# axiom_beta_plugin_module_TE0714_SDI_v0_1.net
KiCad netlist of a schematic drawn in EAGLE
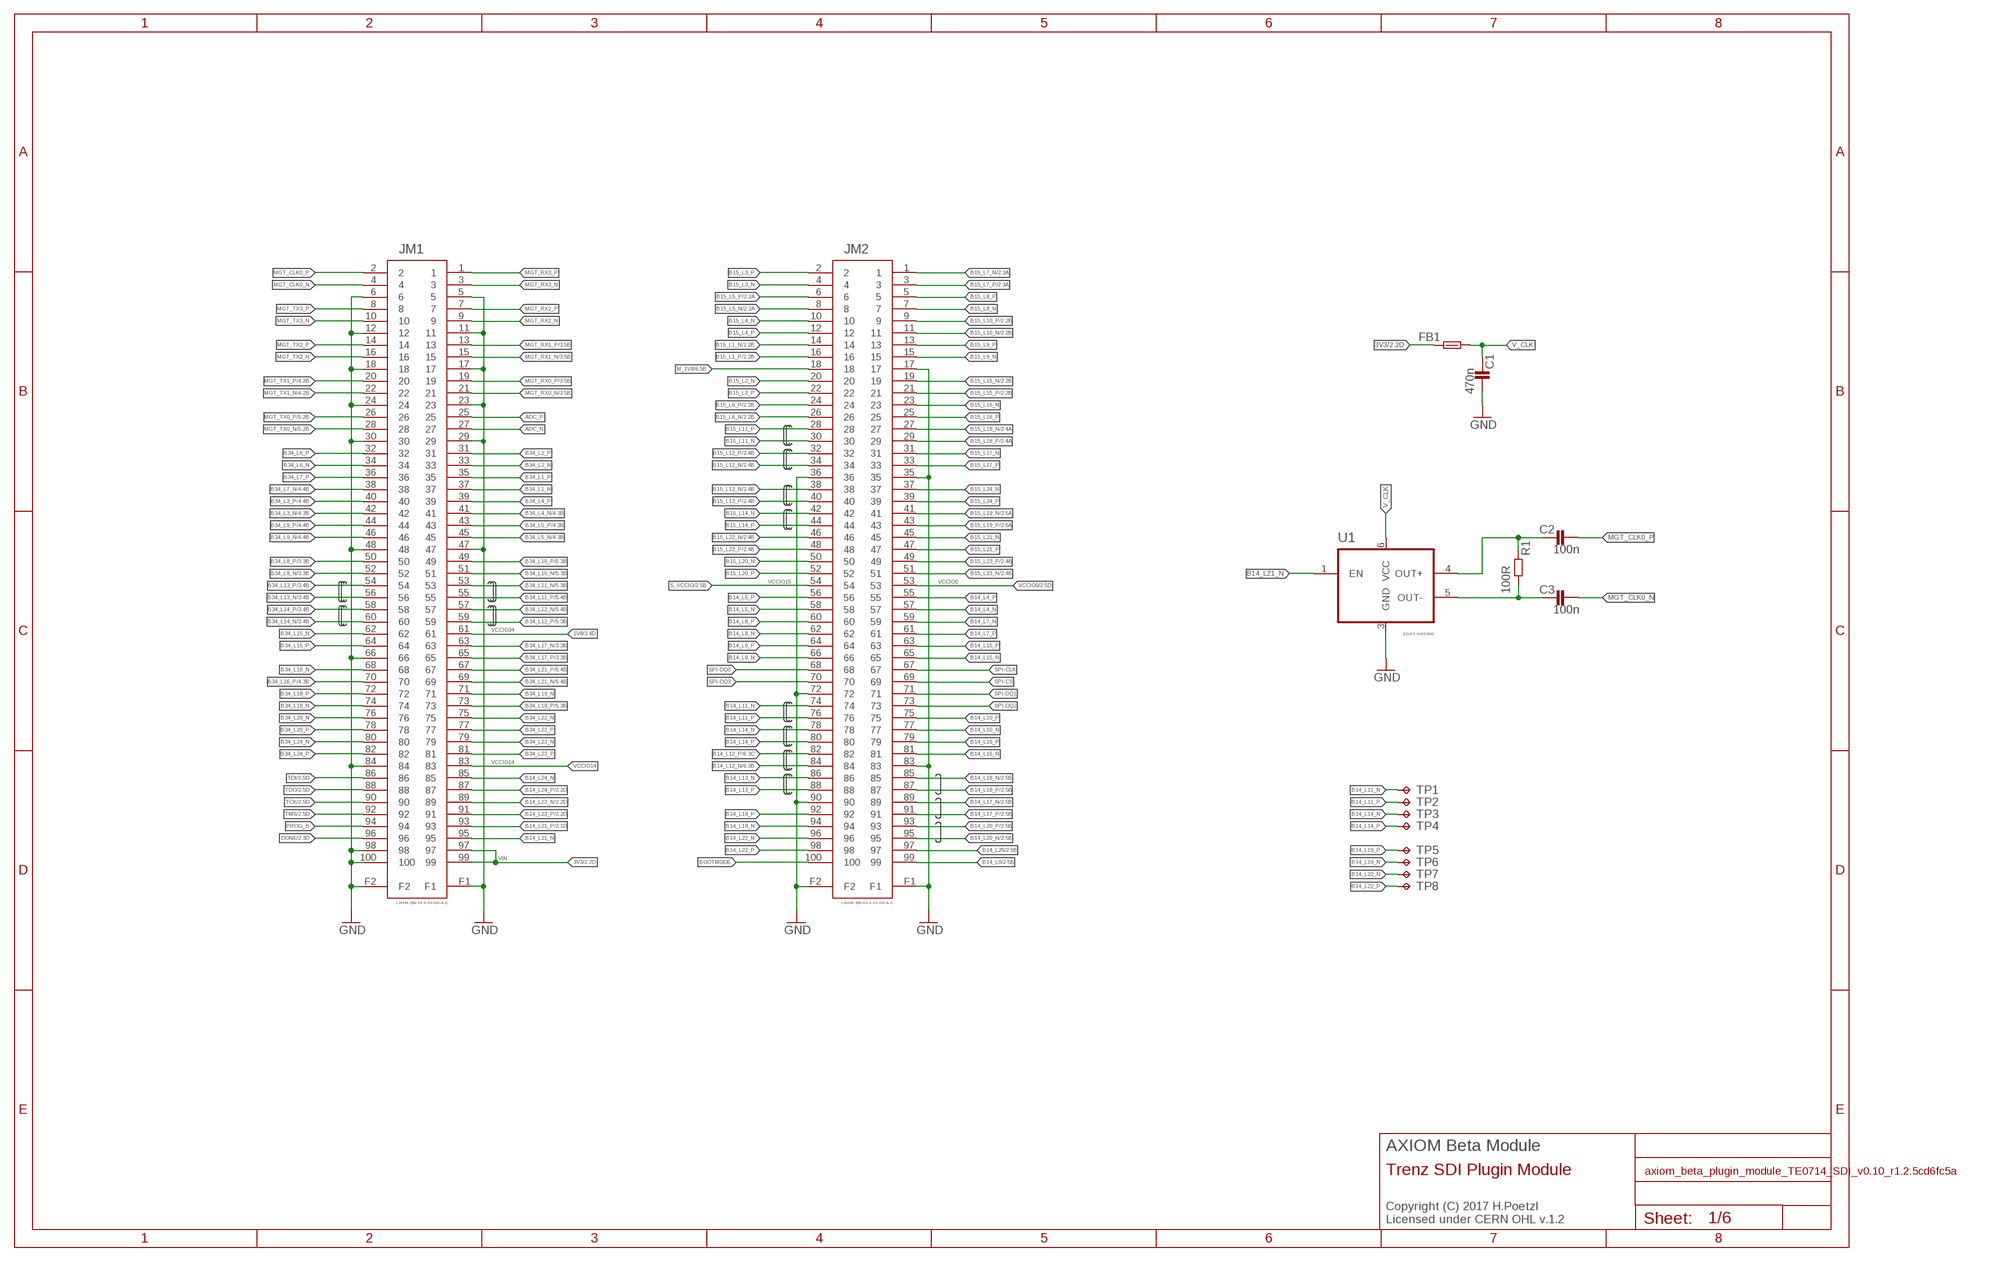
[diagram p0: schematic, sheet 1]
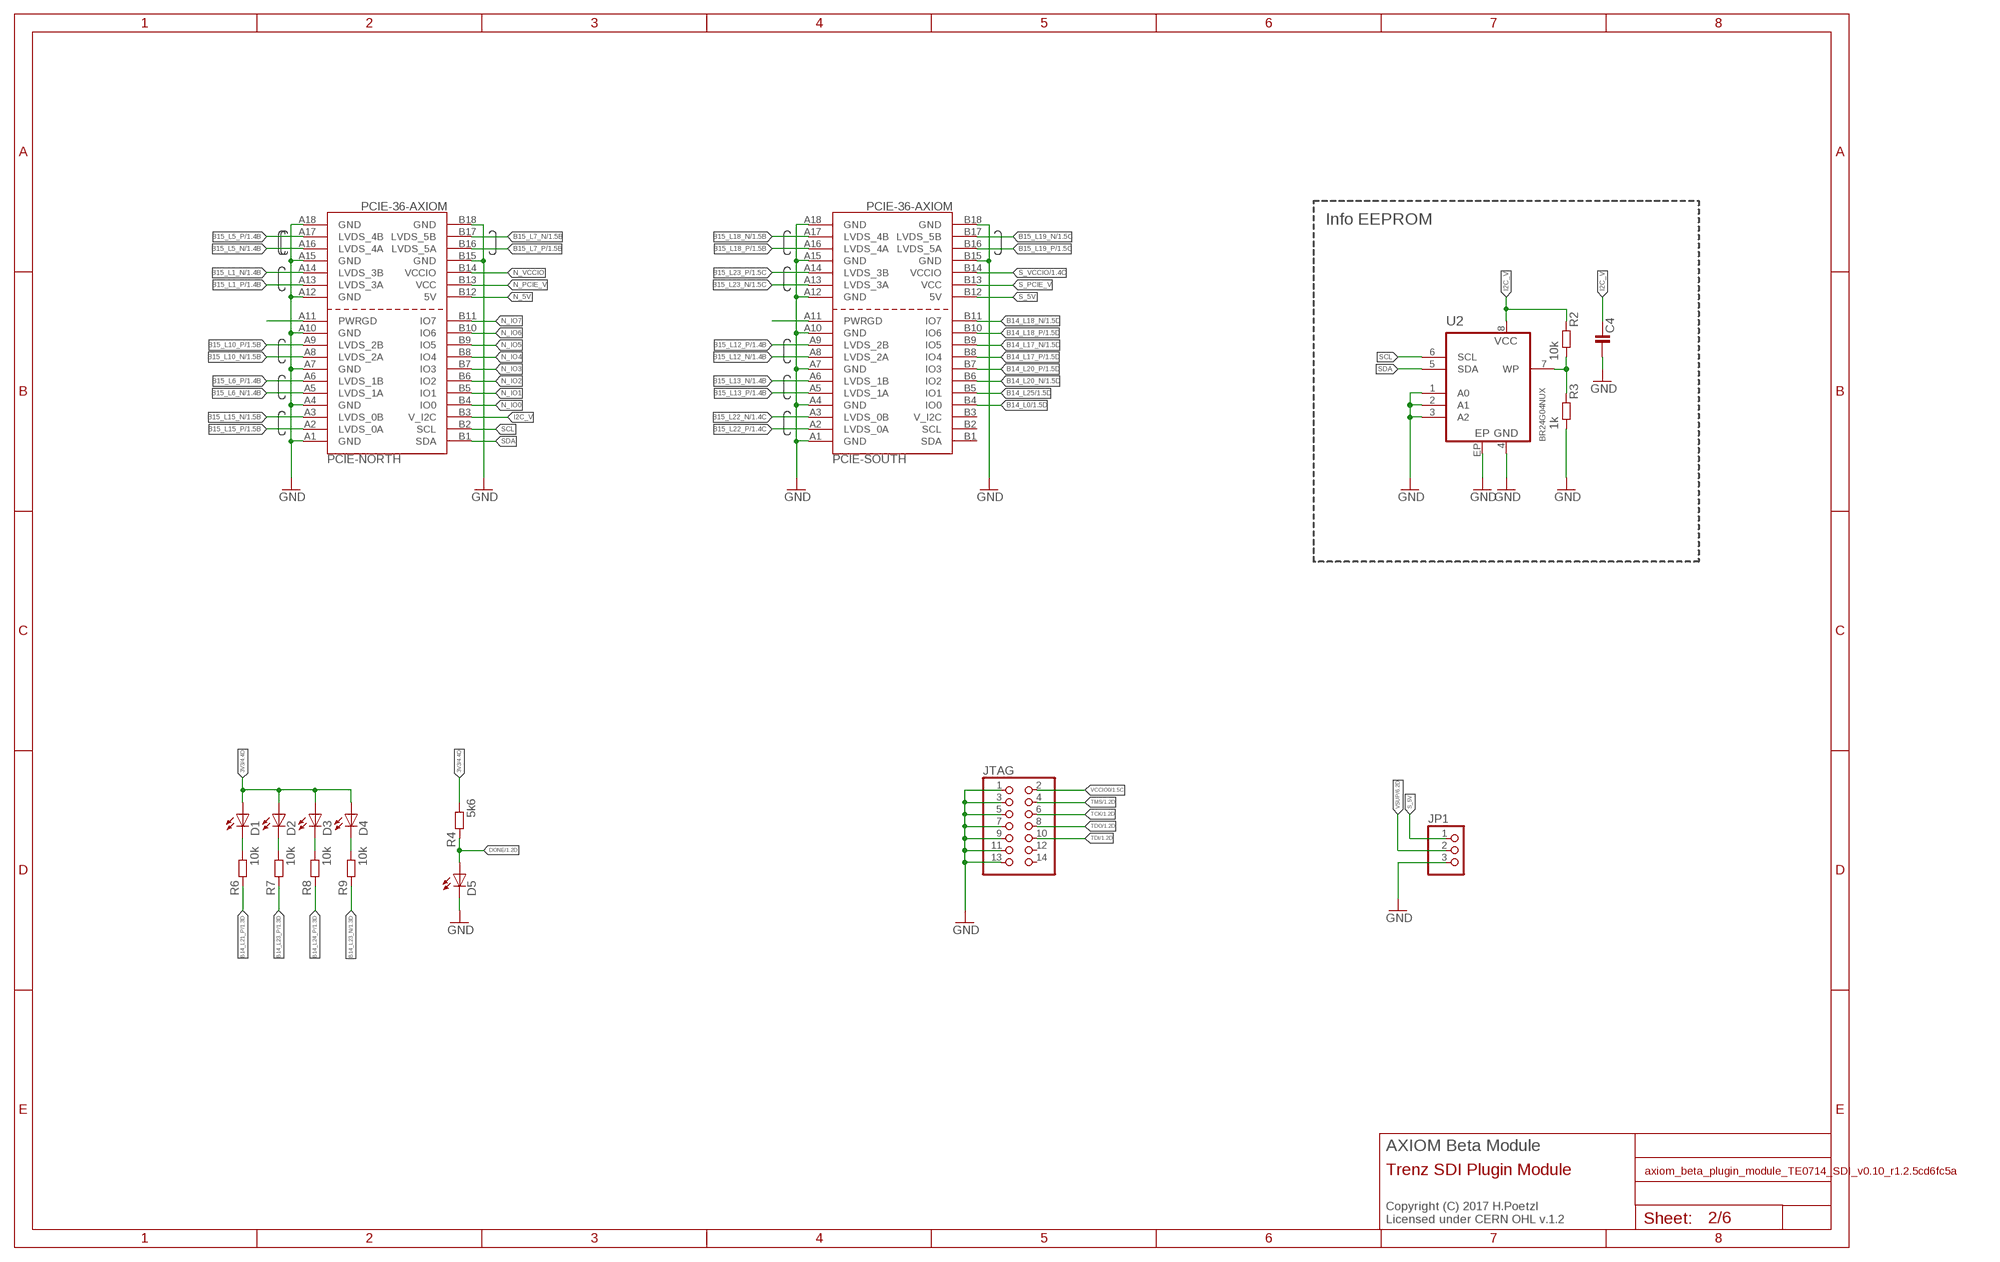
[diagram p1: schematic, sheet 2]
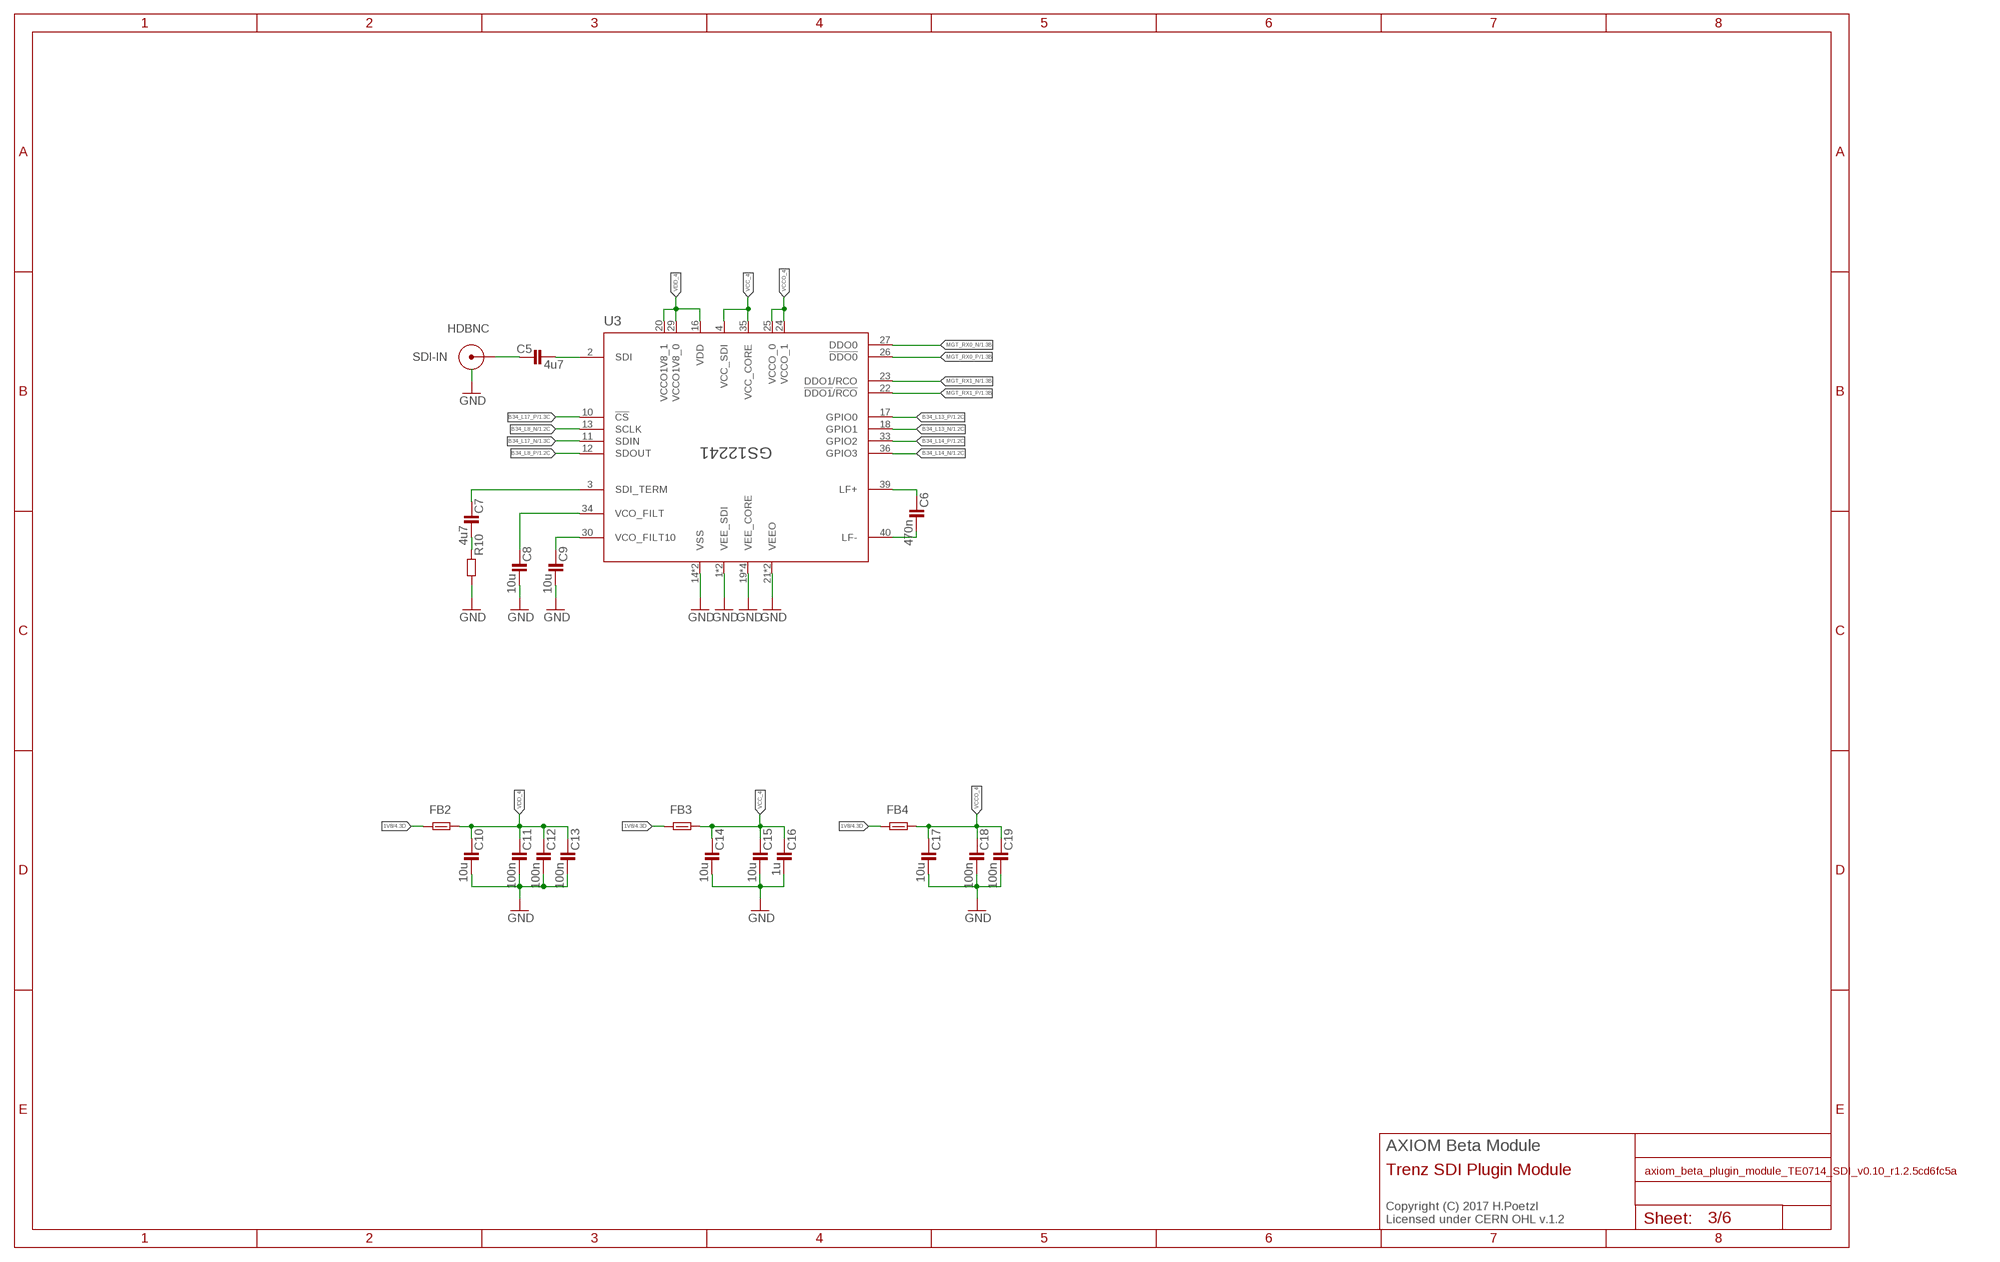
[diagram p2: schematic, sheet 3]
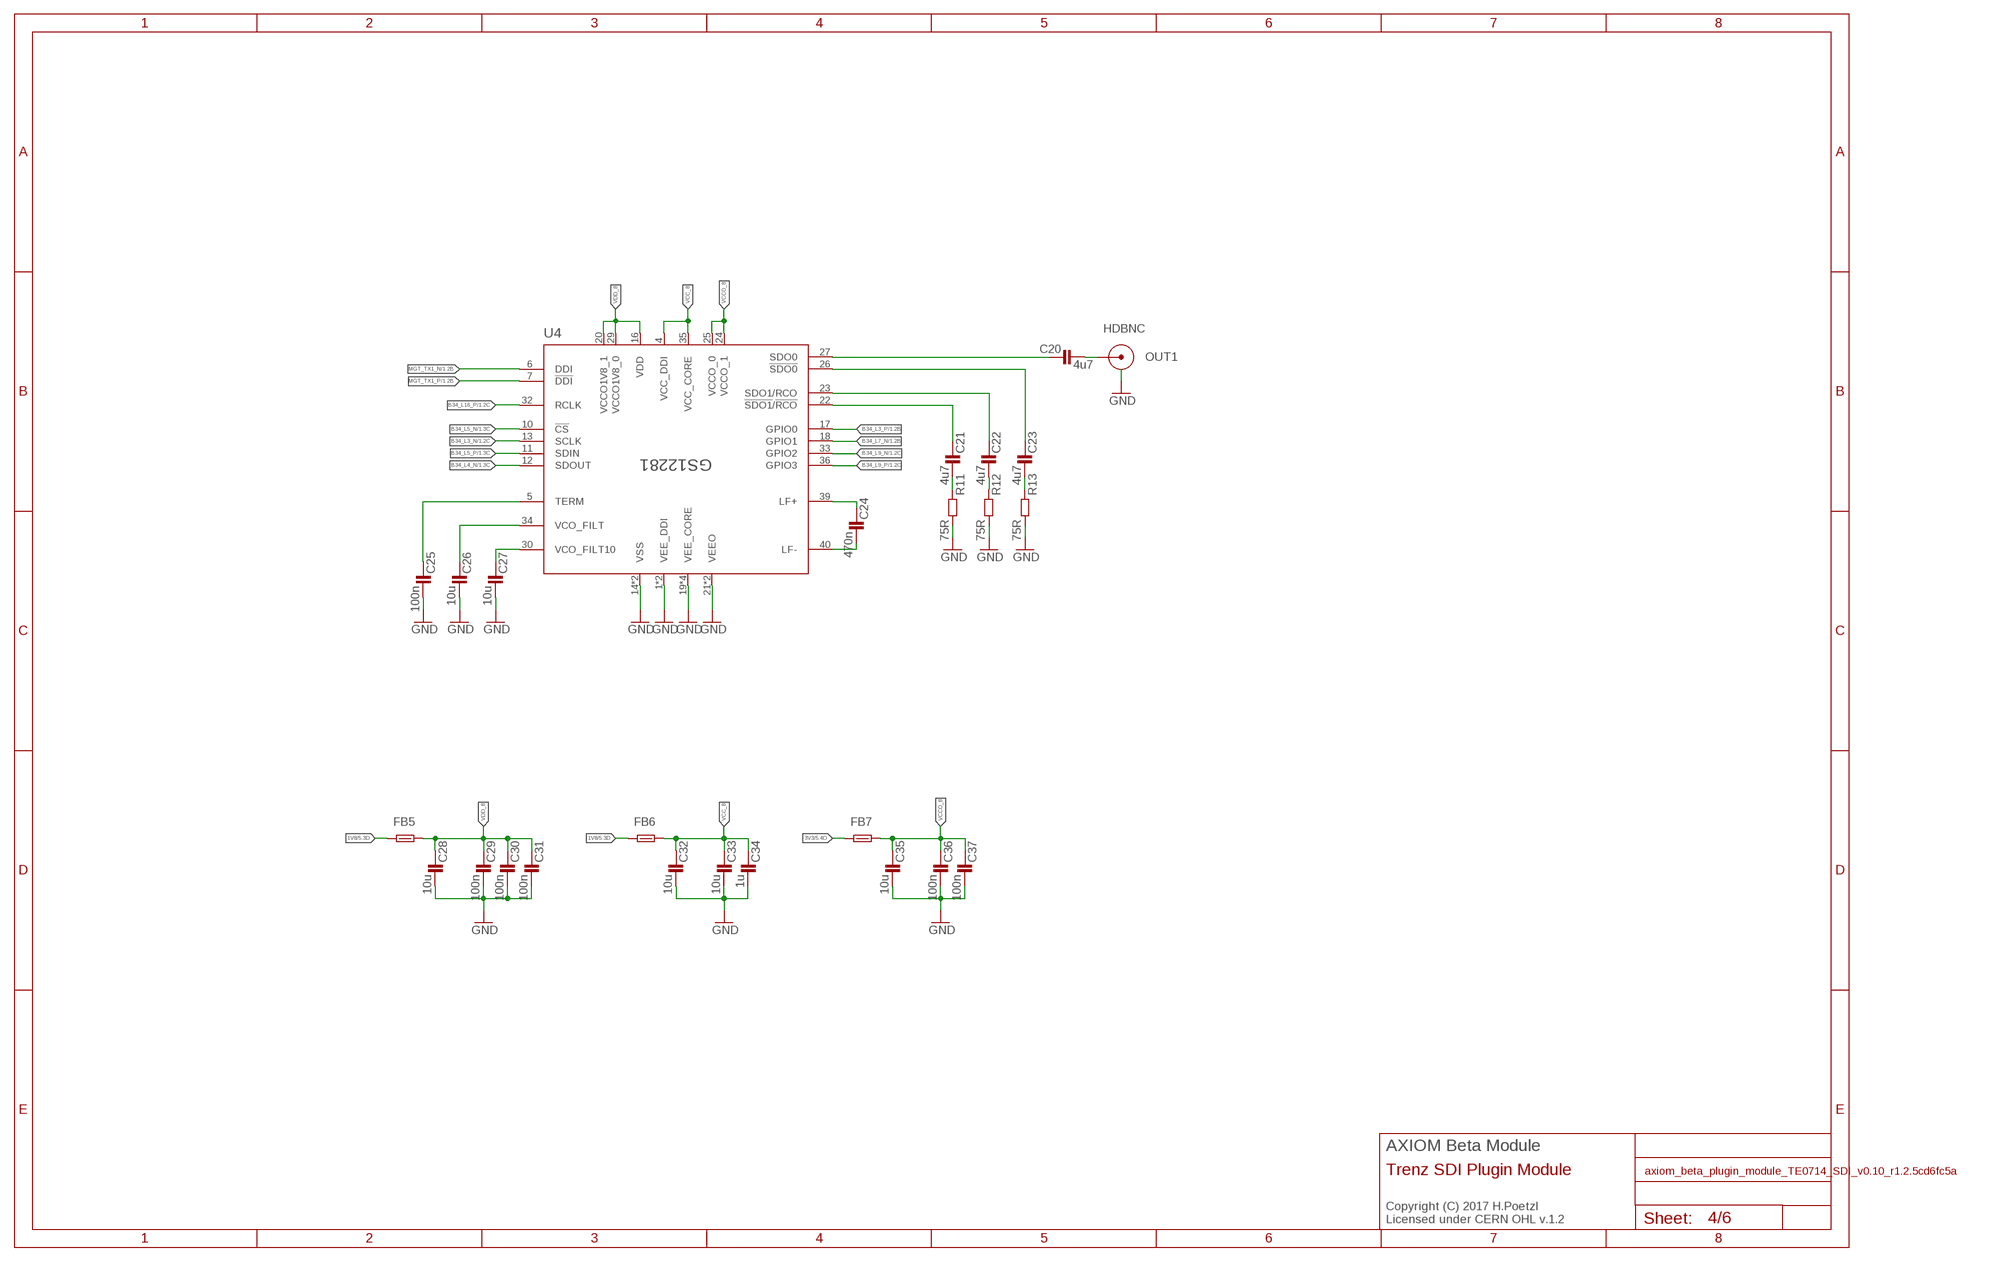
[diagram p3: schematic, sheet 4]
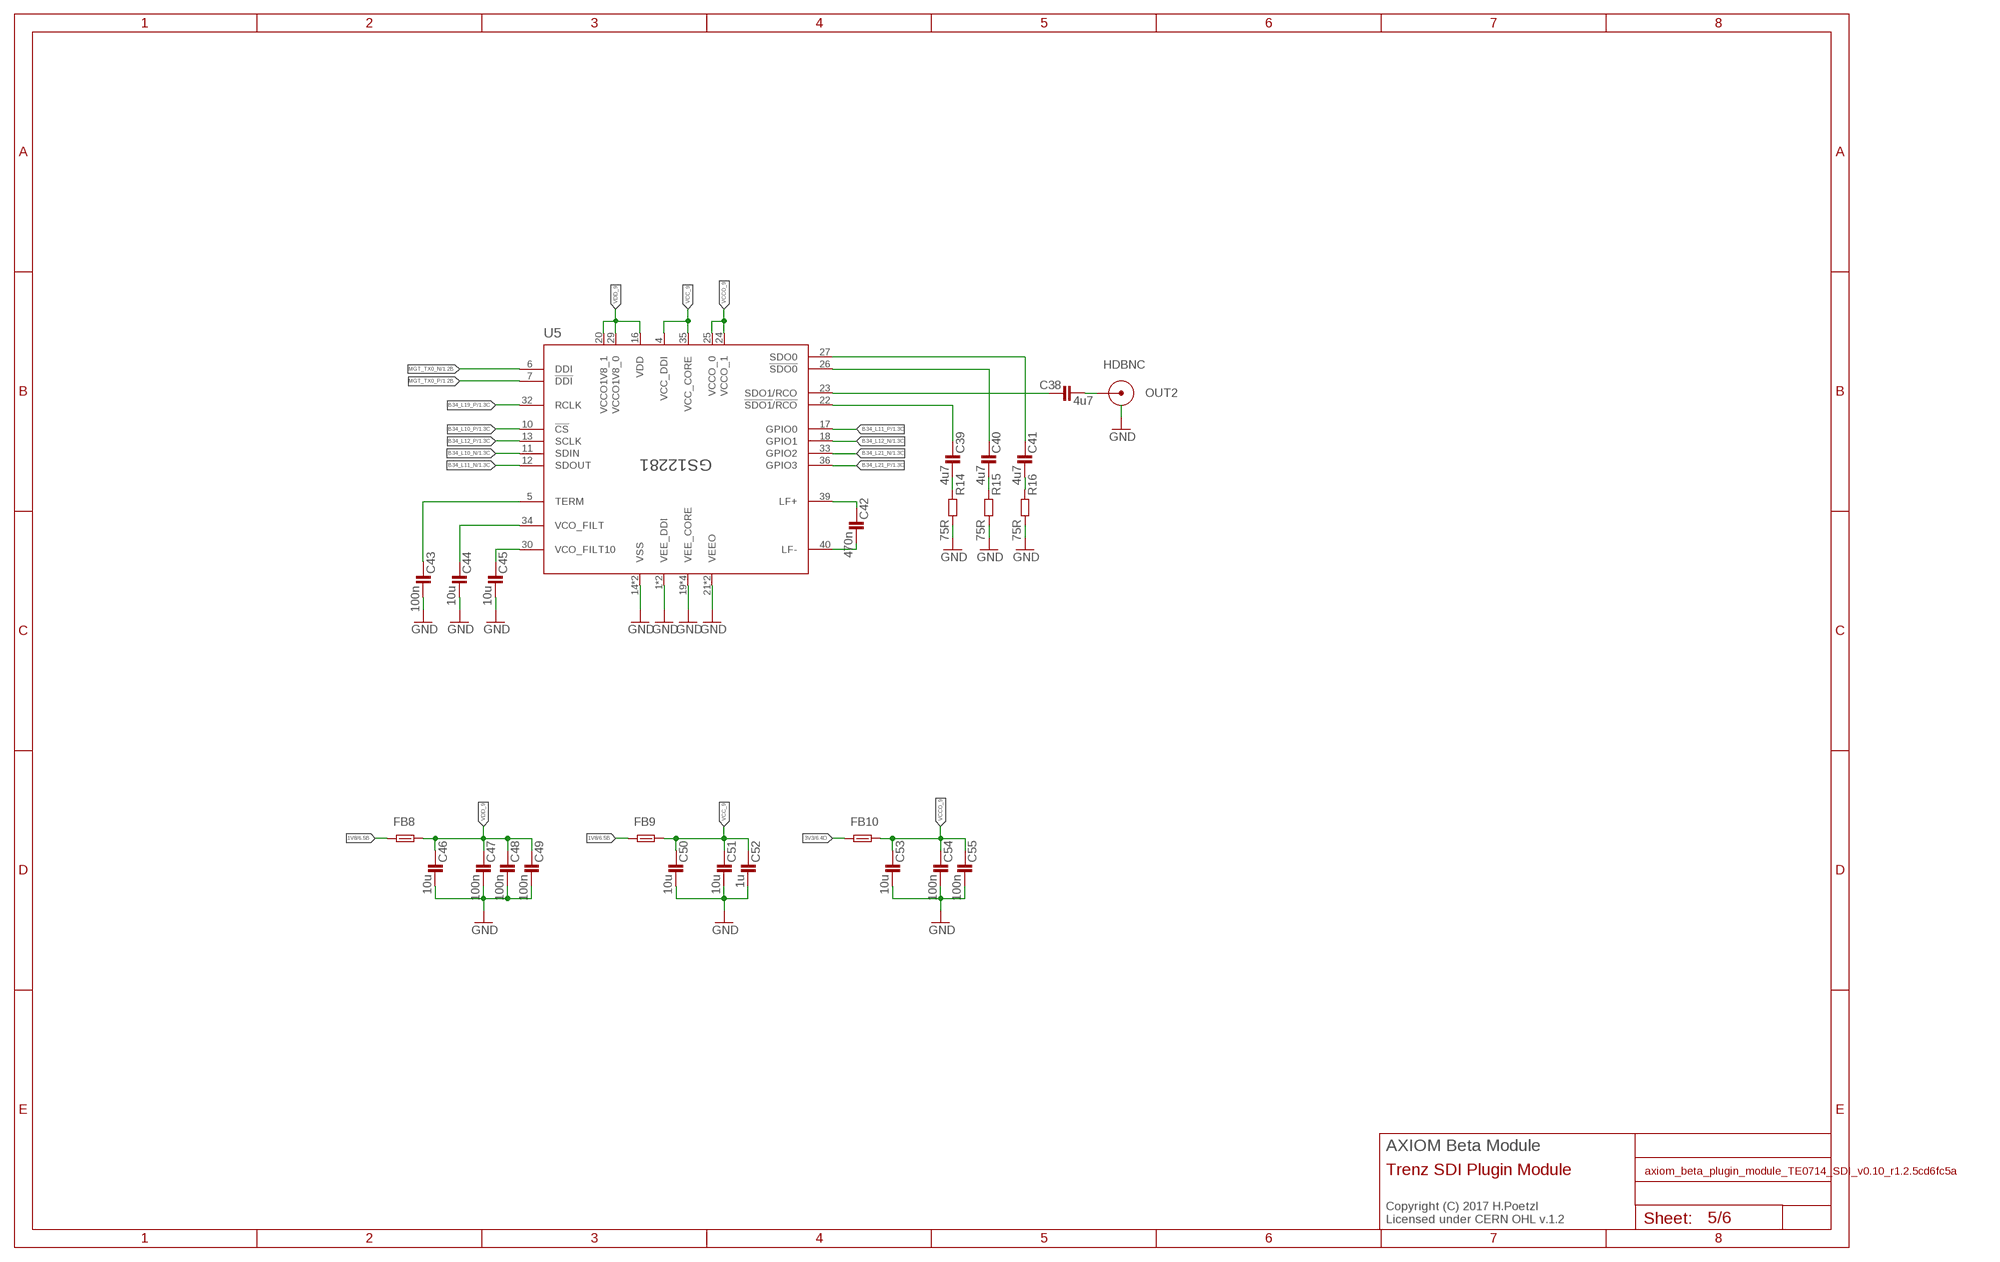
[diagram p4: schematic, sheet 5]
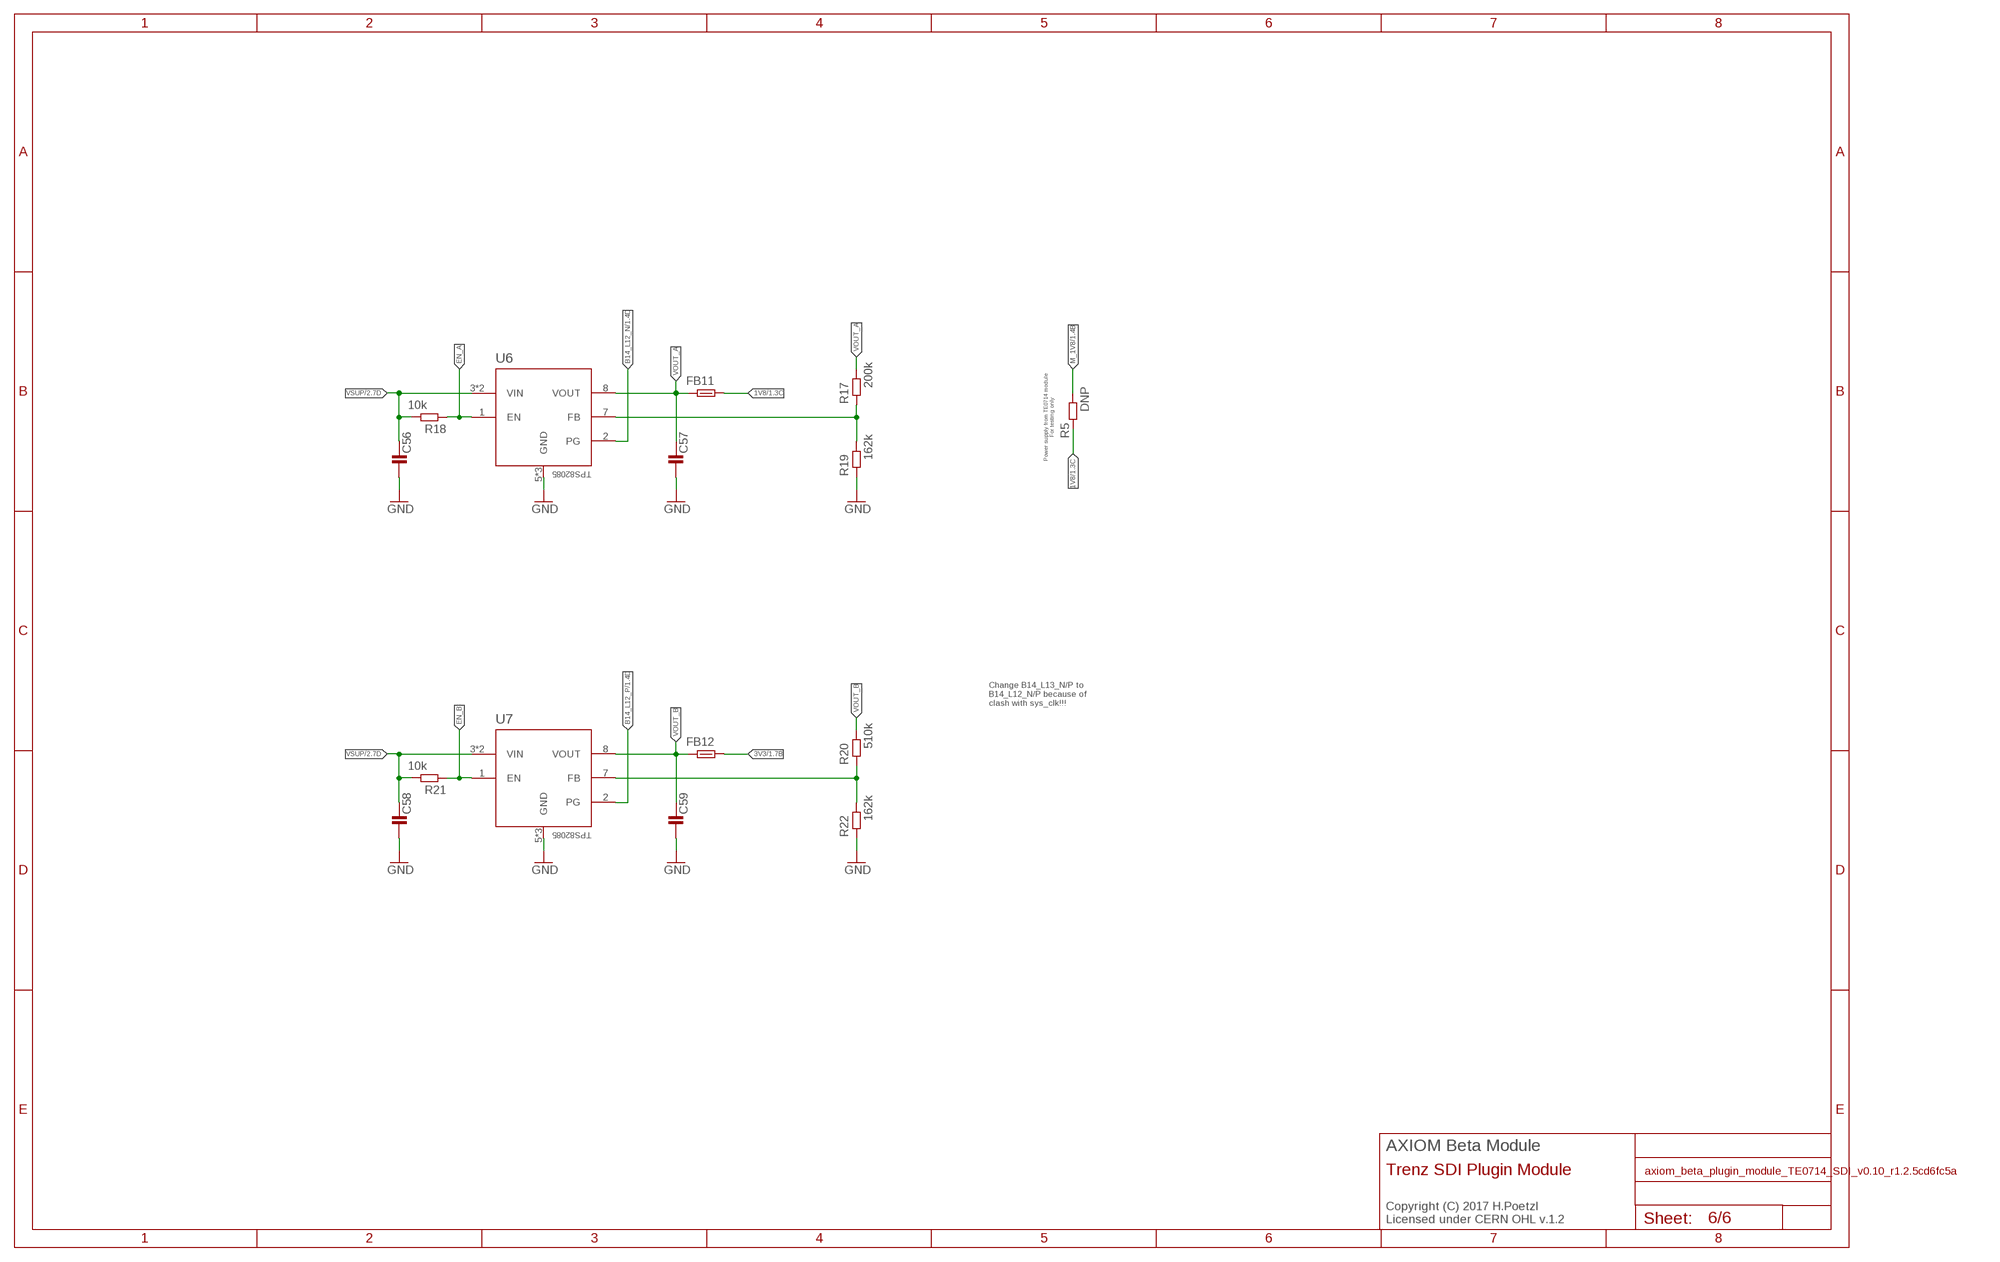
[diagram p5: schematic, sheet 6]

(export (version "E")
  (design (tool "Eeschema 10.0.6"))
  (components
    (comp (ref "C4")
      (value "C0402-B")
      (footprint "eagle-import:0402-B")
      (libsource (lib "eagle-import") (part "C0402-B"))
    )
    (comp (ref "D1")
      (value "LED")
      (footprint "eagle-import:CHIPLED_0603")
      (libsource (lib "eagle-import") (part "LED"))
    )
    (comp (ref "D2")
      (value "LED")
      (footprint "eagle-import:CHIPLED_0603")
      (libsource (lib "eagle-import") (part "LED"))
    )
    (comp (ref "D3")
      (value "LED")
      (footprint "eagle-import:CHIPLED_0603")
      (libsource (lib "eagle-import") (part "LED"))
    )
    (comp (ref "D4")
      (value "LED")
      (footprint "eagle-import:CHIPLED_0603")
      (libsource (lib "eagle-import") (part "LED"))
    )
    (comp (ref "D5")
      (value "LED")
      (footprint "eagle-import:CHIPLED_0603")
      (libsource (lib "eagle-import") (part "LED"))
    )
    (comp (ref "JP1")
      (value "PINHD-1X03_2.54-90°-S")
      (footprint "eagle-import:1X03_90-S")
      (libsource (lib "eagle-import") (part "PINHD-1X03_2.54-90°-S"))
    )
    (comp (ref "JTAG")
      (value "PINHD-2X07_2.00")
      (footprint "eagle-import:2X07M")
      (libsource (lib "eagle-import") (part "PINHD-2X07_2.00"))
    )
    (comp (ref "PCIE-NORTH")
      (value "PCIE-36-AXIOM")
      (footprint "eagle-import:PCIE-36-AXIOM")
      (libsource (lib "eagle-import") (part "PCIE-36-AXIOM"))
    )
    (comp (ref "PCIE-SOUTH")
      (value "PCIE-36-AXIOM")
      (footprint "eagle-import:PCIE-36-AXIOM")
      (libsource (lib "eagle-import") (part "PCIE-36-AXIOM"))
    )
    (comp (ref "R2")
      (value "10k")
      (footprint "eagle-import:0402-B")
      (libsource (lib "eagle-import") (part "R0402-B"))
    )
    (comp (ref "R3")
      (value "1k")
      (footprint "eagle-import:0402-B")
      (libsource (lib "eagle-import") (part "R0402-B"))
    )
    (comp (ref "R4")
      (value "5k6")
      (footprint "eagle-import:0402-C")
      (libsource (lib "eagle-import") (part "R0402-C"))
    )
    (comp (ref "R6")
      (value "10k")
      (footprint "eagle-import:0402-C")
      (libsource (lib "eagle-import") (part "R0402-C"))
    )
    (comp (ref "R7")
      (value "10k")
      (footprint "eagle-import:0402-C")
      (libsource (lib "eagle-import") (part "R0402-C"))
    )
    (comp (ref "R8")
      (value "10k")
      (footprint "eagle-import:0402-C")
      (libsource (lib "eagle-import") (part "R0402-C"))
    )
    (comp (ref "R9")
      (value "10k")
      (footprint "eagle-import:0402-C")
      (libsource (lib "eagle-import") (part "R0402-C"))
    )
    (comp (ref "U2")
      (value "BR24G04NUX")
      (footprint "eagle-import:DFN200X300X100-9N")
      (libsource (lib "eagle-import") (part "BR24G04NUX"))
    )
    (comp (ref "C38")
      (value "4u7")
      (footprint "eagle-import:0402-C")
      (libsource (lib "eagle-import") (part "C0402-C"))
    )
    (comp (ref "C39")
      (value "4u7")
      (footprint "eagle-import:0402-C")
      (libsource (lib "eagle-import") (part "C0402-C"))
    )
    (comp (ref "C40")
      (value "4u7")
      (footprint "eagle-import:0402-C")
      (libsource (lib "eagle-import") (part "C0402-C"))
    )
    (comp (ref "C41")
      (value "4u7")
      (footprint "eagle-import:0402-C")
      (libsource (lib "eagle-import") (part "C0402-C"))
    )
    (comp (ref "C42")
      (value "470n")
      (footprint "eagle-import:0201-C")
      (libsource (lib "eagle-import") (part "C0201-C"))
    )
    (comp (ref "C43")
      (value "100n")
      (footprint "eagle-import:0201-C")
      (libsource (lib "eagle-import") (part "C0201-C"))
    )
    (comp (ref "C44")
      (value "10u")
      (footprint "eagle-import:0402-C")
      (libsource (lib "eagle-import") (part "C0402-C"))
    )
    (comp (ref "C45")
      (value "10u")
      (footprint "eagle-import:0402-C")
      (libsource (lib "eagle-import") (part "C0402-C"))
    )
    (comp (ref "C46")
      (value "10u")
      (footprint "eagle-import:0402-C")
      (libsource (lib "eagle-import") (part "C0402-C"))
    )
    (comp (ref "C47")
      (value "100n")
      (footprint "eagle-import:0201-C")
      (libsource (lib "eagle-import") (part "C0201-C"))
    )
    (comp (ref "C48")
      (value "100n")
      (footprint "eagle-import:0201-C")
      (libsource (lib "eagle-import") (part "C0201-C"))
    )
    (comp (ref "C49")
      (value "100n")
      (footprint "eagle-import:0201-C")
      (libsource (lib "eagle-import") (part "C0201-C"))
    )
    (comp (ref "C50")
      (value "10u")
      (footprint "eagle-import:0402-C")
      (libsource (lib "eagle-import") (part "C0402-C"))
    )
    (comp (ref "C51")
      (value "10u")
      (footprint "eagle-import:0402-C")
      (libsource (lib "eagle-import") (part "C0402-C"))
    )
    (comp (ref "C52")
      (value "1u")
      (footprint "eagle-import:0201-C")
      (libsource (lib "eagle-import") (part "C0201-C"))
    )
    (comp (ref "C53")
      (value "10u")
      (footprint "eagle-import:0402-C")
      (libsource (lib "eagle-import") (part "C0402-C"))
    )
    (comp (ref "C54")
      (value "100n")
      (footprint "eagle-import:0201-C")
      (libsource (lib "eagle-import") (part "C0201-C"))
    )
    (comp (ref "C55")
      (value "100n")
      (footprint "eagle-import:0201-C")
      (libsource (lib "eagle-import") (part "C0201-C"))
    )
    (comp (ref "FB8")
      (value "FB0402-C")
      (footprint "eagle-import:0402-C")
      (libsource (lib "eagle-import") (part "FB0402-C"))
    )
    (comp (ref "FB9")
      (value "FB0402-C")
      (footprint "eagle-import:0402-C")
      (libsource (lib "eagle-import") (part "FB0402-C"))
    )
    (comp (ref "FB10")
      (value "FB0402-C")
      (footprint "eagle-import:0402-C")
      (libsource (lib "eagle-import") (part "FB0402-C"))
    )
    (comp (ref "OUT2")
      (value "HDBNC")
      (footprint "eagle-import:HDBNC_EDGE_2SIDE")
      (libsource (lib "eagle-import") (part "HDBNC"))
    )
    (comp (ref "R14")
      (value "75R")
      (footprint "eagle-import:0201-C")
      (libsource (lib "eagle-import") (part "R0201-C"))
    )
    (comp (ref "R15")
      (value "75R")
      (footprint "eagle-import:0201-C")
      (libsource (lib "eagle-import") (part "R0201-C"))
    )
    (comp (ref "R16")
      (value "75R")
      (footprint "eagle-import:0201-C")
      (libsource (lib "eagle-import") (part "R0201-C"))
    )
    (comp (ref "U5")
      (value "GS12281")
      (footprint "eagle-import:UQFN40P600X400X100-41N")
      (libsource (lib "eagle-import") (part "GS12281"))
    )
    (comp (ref "C1")
      (value "470n")
      (footprint "eagle-import:0402-C")
      (libsource (lib "eagle-import") (part "C0402-C"))
    )
    (comp (ref "C2")
      (value "100n")
      (footprint "eagle-import:0201-C")
      (libsource (lib "eagle-import") (part "C0201-C"))
    )
    (comp (ref "C3")
      (value "100n")
      (footprint "eagle-import:0201-C")
      (libsource (lib "eagle-import") (part "C0201-C"))
    )
    (comp (ref "FB1")
      (value "FB0402-C")
      (footprint "eagle-import:0402-C")
      (libsource (lib "eagle-import") (part "FB0402-C"))
    )
    (comp (ref "JM1")
      (value "LSHM-150-XX.X-XX-DV-A-S")
      (footprint "eagle-import:LSHM-150-XX.X-XX-DV-A-S")
      (libsource (lib "eagle-import") (part "LSHM-150-XX.X-XX-DV-A-S"))
    )
    (comp (ref "JM2")
      (value "LSHM-150-XX.X-XX-DV-A-S")
      (footprint "eagle-import:LSHM-150-XX.X-XX-DV-A-S")
      (libsource (lib "eagle-import") (part "LSHM-150-XX.X-XX-DV-A-S"))
    )
    (comp (ref "R1")
      (value "100R")
      (footprint "eagle-import:0201-C")
      (libsource (lib "eagle-import") (part "R0201-C"))
    )
    (comp (ref "TP1")
      (value "TPTP08R")
      (footprint "eagle-import:TP08R")
      (libsource (lib "eagle-import") (part "TPTP08R"))
    )
    (comp (ref "TP2")
      (value "TPTP08R")
      (footprint "eagle-import:TP08R")
      (libsource (lib "eagle-import") (part "TPTP08R"))
    )
    (comp (ref "TP3")
      (value "TPTP08R")
      (footprint "eagle-import:TP08R")
      (libsource (lib "eagle-import") (part "TPTP08R"))
    )
    (comp (ref "TP4")
      (value "TPTP08R")
      (footprint "eagle-import:TP08R")
      (libsource (lib "eagle-import") (part "TPTP08R"))
    )
    (comp (ref "TP5")
      (value "TPTP10R")
      (footprint "eagle-import:TP10R")
      (libsource (lib "eagle-import") (part "TPTP10R"))
    )
    (comp (ref "TP6")
      (value "TPTP10R")
      (footprint "eagle-import:TP10R")
      (libsource (lib "eagle-import") (part "TPTP10R"))
    )
    (comp (ref "TP7")
      (value "TPTP10R")
      (footprint "eagle-import:TP10R")
      (libsource (lib "eagle-import") (part "TPTP10R"))
    )
    (comp (ref "TP8")
      (value "TPTP10R")
      (footprint "eagle-import:TP10R")
      (libsource (lib "eagle-import") (part "TPTP10R"))
    )
    (comp (ref "U1")
      (value "DSC11XX-3.2X2.5")
      (footprint "eagle-import:3.2X2.5")
      (libsource (lib "eagle-import") (part "DSC11XX-3.2X2.5"))
    )
    (comp (ref "C56")
      (value "C0603-C")
      (footprint "eagle-import:0603-C")
      (libsource (lib "eagle-import") (part "C0603-C"))
    )
    (comp (ref "C57")
      (value "C0603-C")
      (footprint "eagle-import:0603-C")
      (libsource (lib "eagle-import") (part "C0603-C"))
    )
    (comp (ref "C58")
      (value "C0603-C")
      (footprint "eagle-import:0603-C")
      (libsource (lib "eagle-import") (part "C0603-C"))
    )
    (comp (ref "C59")
      (value "C0603-C")
      (footprint "eagle-import:0603-C")
      (libsource (lib "eagle-import") (part "C0603-C"))
    )
    (comp (ref "FB11")
      (value "FB0603-C")
      (footprint "eagle-import:0603-C")
      (libsource (lib "eagle-import") (part "FB0603-C"))
    )
    (comp (ref "FB12")
      (value "FB0603-C")
      (footprint "eagle-import:0603-C")
      (libsource (lib "eagle-import") (part "FB0603-C"))
    )
    (comp (ref "R5")
      (value "DNP")
      (footprint "eagle-import:0402-C")
      (libsource (lib "eagle-import") (part "R0402-C"))
    )
    (comp (ref "R17")
      (value "200k")
      (footprint "eagle-import:0201-C")
      (libsource (lib "eagle-import") (part "R0201-C"))
    )
    (comp (ref "R18")
      (value "10k")
      (footprint "eagle-import:0201-C")
      (libsource (lib "eagle-import") (part "R0201-C"))
    )
    (comp (ref "R19")
      (value "162k")
      (footprint "eagle-import:0201-C")
      (libsource (lib "eagle-import") (part "R0201-C"))
    )
    (comp (ref "R20")
      (value "510k")
      (footprint "eagle-import:0201-C")
      (libsource (lib "eagle-import") (part "R0201-C"))
    )
    (comp (ref "R21")
      (value "10k")
      (footprint "eagle-import:0201-C")
      (libsource (lib "eagle-import") (part "R0201-C"))
    )
    (comp (ref "R22")
      (value "162k")
      (footprint "eagle-import:0201-C")
      (libsource (lib "eagle-import") (part "R0201-C"))
    )
    (comp (ref "U6")
      (value "TPS82085")
      (footprint "eagle-import:MICROSIP")
      (libsource (lib "eagle-import") (part "TPS82085"))
    )
    (comp (ref "U7")
      (value "TPS82085")
      (footprint "eagle-import:MICROSIP")
      (libsource (lib "eagle-import") (part "TPS82085"))
    )
    (comp (ref "C20")
      (value "4u7")
      (footprint "eagle-import:0402-C")
      (libsource (lib "eagle-import") (part "C0402-C"))
    )
    (comp (ref "C21")
      (value "4u7")
      (footprint "eagle-import:0402-C")
      (libsource (lib "eagle-import") (part "C0402-C"))
    )
    (comp (ref "C22")
      (value "4u7")
      (footprint "eagle-import:0402-C")
      (libsource (lib "eagle-import") (part "C0402-C"))
    )
    (comp (ref "C23")
      (value "4u7")
      (footprint "eagle-import:0402-C")
      (libsource (lib "eagle-import") (part "C0402-C"))
    )
    (comp (ref "C24")
      (value "470n")
      (footprint "eagle-import:0201-C")
      (libsource (lib "eagle-import") (part "C0201-C"))
    )
    (comp (ref "C25")
      (value "100n")
      (footprint "eagle-import:0201-C")
      (libsource (lib "eagle-import") (part "C0201-C"))
    )
    (comp (ref "C26")
      (value "10u")
      (footprint "eagle-import:0402-C")
      (libsource (lib "eagle-import") (part "C0402-C"))
    )
    (comp (ref "C27")
      (value "10u")
      (footprint "eagle-import:0402-C")
      (libsource (lib "eagle-import") (part "C0402-C"))
    )
    (comp (ref "C28")
      (value "10u")
      (footprint "eagle-import:0402-C")
      (libsource (lib "eagle-import") (part "C0402-C"))
    )
    (comp (ref "C29")
      (value "100n")
      (footprint "eagle-import:0201-C")
      (libsource (lib "eagle-import") (part "C0201-C"))
    )
    (comp (ref "C30")
      (value "100n")
      (footprint "eagle-import:0201-C")
      (libsource (lib "eagle-import") (part "C0201-C"))
    )
    (comp (ref "C31")
      (value "100n")
      (footprint "eagle-import:0201-C")
      (libsource (lib "eagle-import") (part "C0201-C"))
    )
    (comp (ref "C32")
      (value "10u")
      (footprint "eagle-import:0402-C")
      (libsource (lib "eagle-import") (part "C0402-C"))
    )
    (comp (ref "C33")
      (value "10u")
      (footprint "eagle-import:0402-C")
      (libsource (lib "eagle-import") (part "C0402-C"))
    )
    (comp (ref "C34")
      (value "1u")
      (footprint "eagle-import:0201-C")
      (libsource (lib "eagle-import") (part "C0201-C"))
    )
    (comp (ref "C35")
      (value "10u")
      (footprint "eagle-import:0402-C")
      (libsource (lib "eagle-import") (part "C0402-C"))
    )
    (comp (ref "C36")
      (value "100n")
      (footprint "eagle-import:0201-C")
      (libsource (lib "eagle-import") (part "C0201-C"))
    )
    (comp (ref "C37")
      (value "100n")
      (footprint "eagle-import:0201-C")
      (libsource (lib "eagle-import") (part "C0201-C"))
    )
    (comp (ref "FB5")
      (value "FB0402-C")
      (footprint "eagle-import:0402-C")
      (libsource (lib "eagle-import") (part "FB0402-C"))
    )
    (comp (ref "FB6")
      (value "FB0402-C")
      (footprint "eagle-import:0402-C")
      (libsource (lib "eagle-import") (part "FB0402-C"))
    )
    (comp (ref "FB7")
      (value "FB0402-C")
      (footprint "eagle-import:0402-C")
      (libsource (lib "eagle-import") (part "FB0402-C"))
    )
    (comp (ref "OUT1")
      (value "HDBNC")
      (footprint "eagle-import:HDBNC_EDGE_2SIDE")
      (libsource (lib "eagle-import") (part "HDBNC"))
    )
    (comp (ref "R11")
      (value "75R")
      (footprint "eagle-import:0201-C")
      (libsource (lib "eagle-import") (part "R0201-C"))
    )
    (comp (ref "R12")
      (value "75R")
      (footprint "eagle-import:0201-C")
      (libsource (lib "eagle-import") (part "R0201-C"))
    )
    (comp (ref "R13")
      (value "75R")
      (footprint "eagle-import:0201-C")
      (libsource (lib "eagle-import") (part "R0201-C"))
    )
    (comp (ref "U4")
      (value "GS12281")
      (footprint "eagle-import:UQFN40P600X400X100-41N")
      (libsource (lib "eagle-import") (part "GS12281"))
    )
    (comp (ref "C5")
      (value "4u7")
      (footprint "eagle-import:0402-C")
      (libsource (lib "eagle-import") (part "C0402-C"))
    )
    (comp (ref "C6")
      (value "470n")
      (footprint "eagle-import:0201-C")
      (libsource (lib "eagle-import") (part "C0201-C"))
    )
    (comp (ref "C7")
      (value "4u7")
      (footprint "eagle-import:0402-C")
      (libsource (lib "eagle-import") (part "C0402-C"))
    )
    (comp (ref "C8")
      (value "10u")
      (footprint "eagle-import:0402-C")
      (libsource (lib "eagle-import") (part "C0402-C"))
    )
    (comp (ref "C9")
      (value "10u")
      (footprint "eagle-import:0402-C")
      (libsource (lib "eagle-import") (part "C0402-C"))
    )
    (comp (ref "C10")
      (value "10u")
      (footprint "eagle-import:0402-C")
      (libsource (lib "eagle-import") (part "C0402-C"))
    )
    (comp (ref "C11")
      (value "100n")
      (footprint "eagle-import:0201-C")
      (libsource (lib "eagle-import") (part "C0201-C"))
    )
    (comp (ref "C12")
      (value "100n")
      (footprint "eagle-import:0201-C")
      (libsource (lib "eagle-import") (part "C0201-C"))
    )
    (comp (ref "C13")
      (value "100n")
      (footprint "eagle-import:0201-C")
      (libsource (lib "eagle-import") (part "C0201-C"))
    )
    (comp (ref "C14")
      (value "10u")
      (footprint "eagle-import:0402-C")
      (libsource (lib "eagle-import") (part "C0402-C"))
    )
    (comp (ref "C15")
      (value "10u")
      (footprint "eagle-import:0402-C")
      (libsource (lib "eagle-import") (part "C0402-C"))
    )
    (comp (ref "C16")
      (value "1u")
      (footprint "eagle-import:0201-C")
      (libsource (lib "eagle-import") (part "C0201-C"))
    )
    (comp (ref "C17")
      (value "10u")
      (footprint "eagle-import:0402-C")
      (libsource (lib "eagle-import") (part "C0402-C"))
    )
    (comp (ref "C18")
      (value "100n")
      (footprint "eagle-import:0201-C")
      (libsource (lib "eagle-import") (part "C0201-C"))
    )
    (comp (ref "C19")
      (value "100n")
      (footprint "eagle-import:0201-C")
      (libsource (lib "eagle-import") (part "C0201-C"))
    )
    (comp (ref "FB2")
      (value "FB0402-C")
      (footprint "eagle-import:0402-C")
      (libsource (lib "eagle-import") (part "FB0402-C"))
    )
    (comp (ref "FB3")
      (value "FB0402-C")
      (footprint "eagle-import:0402-C")
      (libsource (lib "eagle-import") (part "FB0402-C"))
    )
    (comp (ref "FB4")
      (value "FB0402-C")
      (footprint "eagle-import:0402-C")
      (libsource (lib "eagle-import") (part "FB0402-C"))
    )
    (comp (ref "R10")
      (value "R0201-C")
      (footprint "eagle-import:0201-C")
      (libsource (lib "eagle-import") (part "R0201-C"))
    )
    (comp (ref "SDI-IN")
      (value "HDBNC")
      (footprint "eagle-import:HDBNC_EDGE_2SIDE")
      (libsource (lib "eagle-import") (part "HDBNC"))
    )
    (comp (ref "U3")
      (value "GS12241")
      (footprint "eagle-import:UQFN40P600X400X100-41N")
      (libsource (lib "eagle-import") (part "GS12241"))
    )
  )
  (nets
    (net (code "1") (name "1V8") (class "Default")
      (node (ref "FB11") (pin "2") (pinfunction "2_2") (pintype "passive"))
      (node (ref "FB2") (pin "1") (pinfunction "1_1") (pintype "passive"))
      (node (ref "FB3") (pin "1") (pinfunction "1_1") (pintype "passive"))
      (node (ref "FB4") (pin "1") (pinfunction "1_1") (pintype "passive"))
      (node (ref "FB5") (pin "1") (pinfunction "1_1") (pintype "passive"))
      (node (ref "FB6") (pin "1") (pinfunction "1_1") (pintype "passive"))
      (node (ref "FB8") (pin "1") (pinfunction "1_1") (pintype "passive"))
      (node (ref "FB9") (pin "1") (pinfunction "1_1") (pintype "passive"))
      (node (ref "JM1") (pin "61") (pinfunction "61_61") (pintype "bidirectional"))
      (node (ref "R5") (pin "1") (pinfunction "1_1") (pintype "passive"))
    )
    (net (code "2") (name "3V3") (class "Default")
      (node (ref "D1") (pin "A") (pinfunction "A_A") (pintype "passive"))
      (node (ref "D2") (pin "A") (pinfunction "A_A") (pintype "passive"))
      (node (ref "D3") (pin "A") (pinfunction "A_A") (pintype "passive"))
      (node (ref "D4") (pin "A") (pinfunction "A_A") (pintype "passive"))
      (node (ref "FB1") (pin "1") (pinfunction "1_1") (pintype "passive"))
      (node (ref "FB10") (pin "1") (pinfunction "1_1") (pintype "passive"))
      (node (ref "FB12") (pin "2") (pinfunction "2_2") (pintype "passive"))
      (node (ref "FB7") (pin "1") (pinfunction "1_1") (pintype "passive"))
      (node (ref "JM1") (pin "97") (pinfunction "97_97") (pintype "bidirectional"))
      (node (ref "JM1") (pin "99") (pinfunction "99_99") (pintype "bidirectional"))
      (node (ref "R4") (pin "2") (pinfunction "2_2") (pintype "passive"))
    )
    (net (code "3") (name "ADC_N") (class "Default")
      (node (ref "JM1") (pin "27") (pinfunction "27_27") (pintype "bidirectional"))
    )
    (net (code "4") (name "ADC_P") (class "Default")
      (node (ref "JM1") (pin "25") (pinfunction "25_25") (pintype "bidirectional"))
    )
    (net (code "5") (name "B14_L0") (class "Default")
      (node (ref "JM2") (pin "99") (pinfunction "99_99") (pintype "bidirectional"))
      (node (ref "PCIE-SOUTH") (pin "B4") (pinfunction "IO0_B4") (pintype "passive"))
    )
    (net (code "6") (name "B14_L4_N") (class "Default")
      (node (ref "JM2") (pin "57") (pinfunction "57_57") (pintype "bidirectional"))
    )
    (net (code "7") (name "B14_L4_P") (class "Default")
      (node (ref "JM2") (pin "55") (pinfunction "55_55") (pintype "bidirectional"))
    )
    (net (code "8") (name "B14_L5_N") (class "Default")
      (node (ref "JM2") (pin "58") (pinfunction "58_58") (pintype "bidirectional"))
    )
    (net (code "9") (name "B14_L5_P") (class "Default")
      (node (ref "JM2") (pin "56") (pinfunction "56_56") (pintype "bidirectional"))
    )
    (net (code "10") (name "B14_L7_N") (class "Default")
      (node (ref "JM2") (pin "59") (pinfunction "59_59") (pintype "bidirectional"))
    )
    (net (code "11") (name "B14_L7_P") (class "Default")
      (node (ref "JM2") (pin "61") (pinfunction "61_61") (pintype "bidirectional"))
    )
    (net (code "12") (name "B14_L8_N") (class "Default")
      (node (ref "JM2") (pin "62") (pinfunction "62_62") (pintype "bidirectional"))
    )
    (net (code "13") (name "B14_L8_P") (class "Default")
      (node (ref "JM2") (pin "60") (pinfunction "60_60") (pintype "bidirectional"))
    )
    (net (code "14") (name "B14_L9_N") (class "Default")
      (node (ref "JM2") (pin "66") (pinfunction "66_66") (pintype "bidirectional"))
    )
    (net (code "15") (name "B14_L9_P") (class "Default")
      (node (ref "JM2") (pin "64") (pinfunction "64_64") (pintype "bidirectional"))
    )
    (net (code "16") (name "B14_L10_N") (class "Default")
      (node (ref "JM2") (pin "77") (pinfunction "77_77") (pintype "bidirectional"))
    )
    (net (code "17") (name "B14_L10_P") (class "Default")
      (node (ref "JM2") (pin "75") (pinfunction "75_75") (pintype "bidirectional"))
    )
    (net (code "18") (name "B14_L11_N") (class "Default")
      (node (ref "JM2") (pin "74") (pinfunction "74_74") (pintype "bidirectional"))
      (node (ref "TP1") (pin "TP") (pinfunction "TP_TP") (pintype "input"))
    )
    (net (code "19") (name "B14_L11_P") (class "Default")
      (node (ref "JM2") (pin "76") (pinfunction "76_76") (pintype "bidirectional"))
      (node (ref "TP2") (pin "TP") (pinfunction "TP_TP") (pintype "input"))
    )
    (net (code "20") (name "B14_L12_N") (class "Default")
      (node (ref "JM2") (pin "84") (pinfunction "84_84") (pintype "bidirectional"))
      (node (ref "U6") (pin "2") (pinfunction "PG_2") (pintype "power_in"))
    )
    (net (code "21") (name "B14_L12_P") (class "Default")
      (node (ref "JM2") (pin "82") (pinfunction "82_82") (pintype "bidirectional"))
      (node (ref "U7") (pin "2") (pinfunction "PG_2") (pintype "power_in"))
    )
    (net (code "22") (name "B14_L13_N") (class "Default")
      (node (ref "JM2") (pin "86") (pinfunction "86_86") (pintype "bidirectional"))
    )
    (net (code "23") (name "B14_L13_P") (class "Default")
      (node (ref "JM2") (pin "88") (pinfunction "88_88") (pintype "bidirectional"))
    )
    (net (code "24") (name "B14_L14_N") (class "Default")
      (node (ref "JM2") (pin "78") (pinfunction "78_78") (pintype "bidirectional"))
      (node (ref "TP3") (pin "TP") (pinfunction "TP_TP") (pintype "input"))
    )
    (net (code "25") (name "B14_L14_P") (class "Default")
      (node (ref "JM2") (pin "80") (pinfunction "80_80") (pintype "bidirectional"))
      (node (ref "TP4") (pin "TP") (pinfunction "TP_TP") (pintype "input"))
    )
    (net (code "26") (name "B14_L15_N") (class "Default")
      (node (ref "JM2") (pin "65") (pinfunction "65_65") (pintype "bidirectional"))
    )
    (net (code "27") (name "B14_L15_P") (class "Default")
      (node (ref "JM2") (pin "63") (pinfunction "63_63") (pintype "bidirectional"))
    )
    (net (code "28") (name "B14_L16_N") (class "Default")
      (node (ref "JM2") (pin "81") (pinfunction "81_81") (pintype "bidirectional"))
    )
    (net (code "29") (name "B14_L16_P") (class "Default")
      (node (ref "JM2") (pin "79") (pinfunction "79_79") (pintype "bidirectional"))
    )
    (net (code "30") (name "B14_L17_N") (class "Default")
      (node (ref "JM2") (pin "89") (pinfunction "89_89") (pintype "bidirectional"))
      (node (ref "PCIE-SOUTH") (pin "B9") (pinfunction "IO5_B9") (pintype "passive"))
    )
    (net (code "31") (name "B14_L17_P") (class "Default")
      (node (ref "JM2") (pin "91") (pinfunction "91_91") (pintype "bidirectional"))
      (node (ref "PCIE-SOUTH") (pin "B8") (pinfunction "IO4_B8") (pintype "passive"))
    )
    (net (code "32") (name "B14_L18_N") (class "Default")
      (node (ref "JM2") (pin "85") (pinfunction "85_85") (pintype "bidirectional"))
      (node (ref "PCIE-SOUTH") (pin "B11") (pinfunction "IO7_B11") (pintype "passive"))
    )
    (net (code "33") (name "B14_L18_P") (class "Default")
      (node (ref "JM2") (pin "87") (pinfunction "87_87") (pintype "bidirectional"))
      (node (ref "PCIE-SOUTH") (pin "B10") (pinfunction "IO6_B10") (pintype "passive"))
    )
    (net (code "34") (name "B14_L19_N") (class "Default")
      (node (ref "JM2") (pin "94") (pinfunction "94_94") (pintype "bidirectional"))
      (node (ref "TP6") (pin "TP") (pinfunction "TP_TP") (pintype "input"))
    )
    (net (code "35") (name "B14_L19_P") (class "Default")
      (node (ref "JM2") (pin "92") (pinfunction "92_92") (pintype "bidirectional"))
      (node (ref "TP5") (pin "TP") (pinfunction "TP_TP") (pintype "input"))
    )
    (net (code "36") (name "B14_L20_N") (class "Default")
      (node (ref "JM2") (pin "95") (pinfunction "95_95") (pintype "bidirectional"))
      (node (ref "PCIE-SOUTH") (pin "B6") (pinfunction "IO2_B6") (pintype "passive"))
    )
    (net (code "37") (name "B14_L20_P") (class "Default")
      (node (ref "JM2") (pin "93") (pinfunction "93_93") (pintype "bidirectional"))
      (node (ref "PCIE-SOUTH") (pin "B7") (pinfunction "IO3_B7") (pintype "passive"))
    )
    (net (code "38") (name "B14_L21_N") (class "Default")
      (node (ref "JM1") (pin "95") (pinfunction "95_95") (pintype "bidirectional"))
      (node (ref "U1") (pin "1") (pinfunction "EN_1") (pintype "input"))
    )
    (net (code "39") (name "B14_L21_P") (class "Default")
      (node (ref "JM1") (pin "93") (pinfunction "93_93") (pintype "bidirectional"))
      (node (ref "R6") (pin "1") (pinfunction "1_1") (pintype "passive"))
    )
    (net (code "40") (name "B14_L22_N") (class "Default")
      (node (ref "JM2") (pin "96") (pinfunction "96_96") (pintype "bidirectional"))
      (node (ref "TP7") (pin "TP") (pinfunction "TP_TP") (pintype "input"))
    )
    (net (code "41") (name "B14_L22_P") (class "Default")
      (node (ref "JM2") (pin "98") (pinfunction "98_98") (pintype "bidirectional"))
      (node (ref "TP8") (pin "TP") (pinfunction "TP_TP") (pintype "input"))
    )
    (net (code "42") (name "B14_L23_N") (class "Default")
      (node (ref "JM1") (pin "89") (pinfunction "89_89") (pintype "bidirectional"))
      (node (ref "R9") (pin "1") (pinfunction "1_1") (pintype "passive"))
    )
    (net (code "43") (name "B14_L23_P") (class "Default")
      (node (ref "JM1") (pin "91") (pinfunction "91_91") (pintype "bidirectional"))
      (node (ref "R7") (pin "1") (pinfunction "1_1") (pintype "passive"))
    )
    (net (code "44") (name "B14_L24_N") (class "Default")
      (node (ref "JM1") (pin "85") (pinfunction "85_85") (pintype "bidirectional"))
    )
    (net (code "45") (name "B14_L24_P") (class "Default")
      (node (ref "JM1") (pin "87") (pinfunction "87_87") (pintype "bidirectional"))
      (node (ref "R8") (pin "1") (pinfunction "1_1") (pintype "passive"))
    )
    (net (code "46") (name "B14_L25") (class "Default")
      (node (ref "JM2") (pin "97") (pinfunction "97_97") (pintype "bidirectional"))
      (node (ref "PCIE-SOUTH") (pin "B5") (pinfunction "IO1_B5") (pintype "passive"))
    )
    (net (code "47") (name "B15_L1_N") (class "Default")
      (node (ref "JM2") (pin "14") (pinfunction "14_14") (pintype "bidirectional"))
      (node (ref "PCIE-NORTH") (pin "A14") (pinfunction "LVDS_3B_A14") (pintype "passive"))
    )
    (net (code "48") (name "B15_L1_P") (class "Default")
      (node (ref "JM2") (pin "16") (pinfunction "16_16") (pintype "bidirectional"))
      (node (ref "PCIE-NORTH") (pin "A13") (pinfunction "LVDS_3A_A13") (pintype "passive"))
    )
    (net (code "49") (name "B15_L2_N") (class "Default")
      (node (ref "JM2") (pin "20") (pinfunction "20_20") (pintype "bidirectional"))
    )
    (net (code "50") (name "B15_L2_P") (class "Default")
      (node (ref "JM2") (pin "22") (pinfunction "22_22") (pintype "bidirectional"))
    )
    (net (code "51") (name "B15_L3_N") (class "Default")
      (node (ref "JM2") (pin "4") (pinfunction "4_4") (pintype "bidirectional"))
    )
    (net (code "52") (name "B15_L3_P") (class "Default")
      (node (ref "JM2") (pin "2") (pinfunction "2_2") (pintype "bidirectional"))
    )
    (net (code "53") (name "B15_L4_N") (class "Default")
      (node (ref "JM2") (pin "10") (pinfunction "10_10") (pintype "bidirectional"))
    )
    (net (code "54") (name "B15_L4_P") (class "Default")
      (node (ref "JM2") (pin "12") (pinfunction "12_12") (pintype "bidirectional"))
    )
    (net (code "55") (name "B15_L5_N") (class "Default")
      (node (ref "JM2") (pin "8") (pinfunction "8_8") (pintype "bidirectional"))
      (node (ref "PCIE-NORTH") (pin "A16") (pinfunction "LVDS_4A_A16") (pintype "passive"))
    )
    (net (code "56") (name "B15_L5_P") (class "Default")
      (node (ref "JM2") (pin "6") (pinfunction "6_6") (pintype "bidirectional"))
      (node (ref "PCIE-NORTH") (pin "A17") (pinfunction "LVDS_4B_A17") (pintype "passive"))
    )
    (net (code "57") (name "B15_L6_N") (class "Default")
      (node (ref "JM2") (pin "26") (pinfunction "26_26") (pintype "bidirectional"))
      (node (ref "PCIE-NORTH") (pin "A5") (pinfunction "LVDS_1A_A5") (pintype "passive"))
    )
    (net (code "58") (name "B15_L6_P") (class "Default")
      (node (ref "JM2") (pin "24") (pinfunction "24_24") (pintype "bidirectional"))
      (node (ref "PCIE-NORTH") (pin "A6") (pinfunction "LVDS_1B_A6") (pintype "passive"))
    )
    (net (code "59") (name "B15_L7_N") (class "Default")
      (node (ref "JM2") (pin "1") (pinfunction "1_1") (pintype "bidirectional"))
      (node (ref "PCIE-NORTH") (pin "B17") (pinfunction "LVDS_5B_B17") (pintype "passive"))
    )
    (net (code "60") (name "B15_L7_P") (class "Default")
      (node (ref "JM2") (pin "3") (pinfunction "3_3") (pintype "bidirectional"))
      (node (ref "PCIE-NORTH") (pin "B16") (pinfunction "LVDS_5A_B16") (pintype "passive"))
    )
    (net (code "61") (name "B15_L8_N") (class "Default")
      (node (ref "JM2") (pin "7") (pinfunction "7_7") (pintype "bidirectional"))
    )
    (net (code "62") (name "B15_L8_P") (class "Default")
      (node (ref "JM2") (pin "5") (pinfunction "5_5") (pintype "bidirectional"))
    )
    (net (code "63") (name "B15_L9_N") (class "Default")
      (node (ref "JM2") (pin "15") (pinfunction "15_15") (pintype "bidirectional"))
    )
    (net (code "64") (name "B15_L9_P") (class "Default")
      (node (ref "JM2") (pin "13") (pinfunction "13_13") (pintype "bidirectional"))
    )
    (net (code "65") (name "B15_L10_N") (class "Default")
      (node (ref "JM2") (pin "11") (pinfunction "11_11") (pintype "bidirectional"))
      (node (ref "PCIE-NORTH") (pin "A8") (pinfunction "LVDS_2A_A8") (pintype "passive"))
    )
    (net (code "66") (name "B15_L10_P") (class "Default")
      (node (ref "JM2") (pin "9") (pinfunction "9_9") (pintype "bidirectional"))
      (node (ref "PCIE-NORTH") (pin "A9") (pinfunction "LVDS_2B_A9") (pintype "passive"))
    )
    (net (code "67") (name "B15_L11_N") (class "Default")
      (node (ref "JM2") (pin "30") (pinfunction "30_30") (pintype "bidirectional"))
    )
    (net (code "68") (name "B15_L11_P") (class "Default")
      (node (ref "JM2") (pin "28") (pinfunction "28_28") (pintype "bidirectional"))
    )
    (net (code "69") (name "B15_L12_N") (class "Default")
      (node (ref "JM2") (pin "34") (pinfunction "34_34") (pintype "bidirectional"))
      (node (ref "PCIE-SOUTH") (pin "A8") (pinfunction "LVDS_2A_A8") (pintype "passive"))
    )
    (net (code "70") (name "B15_L12_P") (class "Default")
      (node (ref "JM2") (pin "32") (pinfunction "32_32") (pintype "bidirectional"))
      (node (ref "PCIE-SOUTH") (pin "A9") (pinfunction "LVDS_2B_A9") (pintype "passive"))
    )
    (net (code "71") (name "B15_L13_N") (class "Default")
      (node (ref "JM2") (pin "38") (pinfunction "38_38") (pintype "bidirectional"))
      (node (ref "PCIE-SOUTH") (pin "A6") (pinfunction "LVDS_1B_A6") (pintype "passive"))
    )
    (net (code "72") (name "B15_L13_P") (class "Default")
      (node (ref "JM2") (pin "40") (pinfunction "40_40") (pintype "bidirectional"))
      (node (ref "PCIE-SOUTH") (pin "A5") (pinfunction "LVDS_1A_A5") (pintype "passive"))
    )
    (net (code "73") (name "B15_L14_N") (class "Default")
      (node (ref "JM2") (pin "42") (pinfunction "42_42") (pintype "bidirectional"))
    )
    (net (code "74") (name "B15_L14_P") (class "Default")
      (node (ref "JM2") (pin "44") (pinfunction "44_44") (pintype "bidirectional"))
    )
    (net (code "75") (name "B15_L15_N") (class "Default")
      (node (ref "JM2") (pin "19") (pinfunction "19_19") (pintype "bidirectional"))
      (node (ref "PCIE-NORTH") (pin "A3") (pinfunction "LVDS_0B_A3") (pintype "passive"))
    )
    (net (code "76") (name "B15_L15_P") (class "Default")
      (node (ref "JM2") (pin "21") (pinfunction "21_21") (pintype "bidirectional"))
      (node (ref "PCIE-NORTH") (pin "A2") (pinfunction "LVDS_0A_A2") (pintype "passive"))
    )
    (net (code "77") (name "B15_L16_N") (class "Default")
      (node (ref "JM2") (pin "23") (pinfunction "23_23") (pintype "bidirectional"))
    )
    (net (code "78") (name "B15_L16_P") (class "Default")
      (node (ref "JM2") (pin "25") (pinfunction "25_25") (pintype "bidirectional"))
    )
    (net (code "79") (name "B15_L17_N") (class "Default")
      (node (ref "JM2") (pin "31") (pinfunction "31_31") (pintype "bidirectional"))
    )
    (net (code "80") (name "B15_L17_P") (class "Default")
      (node (ref "JM2") (pin "33") (pinfunction "33_33") (pintype "bidirectional"))
    )
    (net (code "81") (name "B15_L18_N") (class "Default")
      (node (ref "JM2") (pin "27") (pinfunction "27_27") (pintype "bidirectional"))
      (node (ref "PCIE-SOUTH") (pin "A17") (pinfunction "LVDS_4B_A17") (pintype "passive"))
    )
    (net (code "82") (name "B15_L18_P") (class "Default")
      (node (ref "JM2") (pin "29") (pinfunction "29_29") (pintype "bidirectional"))
      (node (ref "PCIE-SOUTH") (pin "A16") (pinfunction "LVDS_4A_A16") (pintype "passive"))
    )
    (net (code "83") (name "B15_L19_N") (class "Default")
      (node (ref "JM2") (pin "41") (pinfunction "41_41") (pintype "bidirectional"))
      (node (ref "PCIE-SOUTH") (pin "B17") (pinfunction "LVDS_5B_B17") (pintype "passive"))
    )
    (net (code "84") (name "B15_L19_P") (class "Default")
      (node (ref "JM2") (pin "43") (pinfunction "43_43") (pintype "bidirectional"))
      (node (ref "PCIE-SOUTH") (pin "B16") (pinfunction "LVDS_5A_B16") (pintype "passive"))
    )
    (net (code "85") (name "B15_L20_N") (class "Default")
      (node (ref "JM2") (pin "50") (pinfunction "50_50") (pintype "bidirectional"))
    )
    (net (code "86") (name "B15_L20_P") (class "Default")
      (node (ref "JM2") (pin "52") (pinfunction "52_52") (pintype "bidirectional"))
    )
    (net (code "87") (name "B15_L21_N") (class "Default")
      (node (ref "JM2") (pin "45") (pinfunction "45_45") (pintype "bidirectional"))
    )
    (net (code "88") (name "B15_L21_P") (class "Default")
      (node (ref "JM2") (pin "47") (pinfunction "47_47") (pintype "bidirectional"))
    )
    (net (code "89") (name "B15_L22_N") (class "Default")
      (node (ref "JM2") (pin "46") (pinfunction "46_46") (pintype "bidirectional"))
      (node (ref "PCIE-SOUTH") (pin "A3") (pinfunction "LVDS_0B_A3") (pintype "passive"))
    )
    (net (code "90") (name "B15_L22_P") (class "Default")
      (node (ref "JM2") (pin "48") (pinfunction "48_48") (pintype "bidirectional"))
      (node (ref "PCIE-SOUTH") (pin "A2") (pinfunction "LVDS_0A_A2") (pintype "passive"))
    )
    (net (code "91") (name "B15_L23_N") (class "Default")
      (node (ref "JM2") (pin "51") (pinfunction "51_51") (pintype "bidirectional"))
      (node (ref "PCIE-SOUTH") (pin "A13") (pinfunction "LVDS_3A_A13") (pintype "passive"))
    )
    (net (code "92") (name "B15_L23_P") (class "Default")
      (node (ref "JM2") (pin "49") (pinfunction "49_49") (pintype "bidirectional"))
      (node (ref "PCIE-SOUTH") (pin "A14") (pinfunction "LVDS_3B_A14") (pintype "passive"))
    )
    (net (code "93") (name "B15_L24_N") (class "Default")
      (node (ref "JM2") (pin "37") (pinfunction "37_37") (pintype "bidirectional"))
    )
    (net (code "94") (name "B15_L24_P") (class "Default")
      (node (ref "JM2") (pin "39") (pinfunction "39_39") (pintype "bidirectional"))
    )
    (net (code "95") (name "B34_L1_N") (class "Default")
      (node (ref "JM1") (pin "37") (pinfunction "37_37") (pintype "bidirectional"))
    )
    (net (code "96") (name "B34_L1_P") (class "Default")
      (node (ref "JM1") (pin "35") (pinfunction "35_35") (pintype "bidirectional"))
    )
    (net (code "97") (name "B34_L2_N") (class "Default")
      (node (ref "JM1") (pin "33") (pinfunction "33_33") (pintype "bidirectional"))
    )
    (net (code "98") (name "B34_L2_P") (class "Default")
      (node (ref "JM1") (pin "31") (pinfunction "31_31") (pintype "bidirectional"))
    )
    (net (code "99") (name "B34_L3_N") (class "Default")
      (node (ref "JM1") (pin "42") (pinfunction "42_42") (pintype "bidirectional"))
      (node (ref "U4") (pin "13") (pinfunction "SCLK_13") (pintype "input"))
    )
    (net (code "100") (name "B34_L3_P") (class "Default")
      (node (ref "JM1") (pin "40") (pinfunction "40_40") (pintype "bidirectional"))
      (node (ref "U4") (pin "17") (pinfunction "GPIO0_17") (pintype "bidirectional"))
    )
    (net (code "101") (name "B34_L4_N") (class "Default")
      (node (ref "JM1") (pin "41") (pinfunction "41_41") (pintype "bidirectional"))
      (node (ref "U4") (pin "12") (pinfunction "SDOUT_12") (pintype "output"))
    )
    (net (code "102") (name "B34_L4_P") (class "Default")
      (node (ref "JM1") (pin "39") (pinfunction "39_39") (pintype "bidirectional"))
    )
    (net (code "103") (name "B34_L5_N") (class "Default")
      (node (ref "JM1") (pin "45") (pinfunction "45_45") (pintype "bidirectional"))
      (node (ref "U4") (pin "10") (pinfunction "~{CS}_10") (pintype "input"))
    )
    (net (code "104") (name "B34_L5_P") (class "Default")
      (node (ref "JM1") (pin "43") (pinfunction "43_43") (pintype "bidirectional"))
      (node (ref "U4") (pin "11") (pinfunction "SDIN_11") (pintype "input"))
    )
    (net (code "105") (name "B34_L6_N") (class "Default")
      (node (ref "JM1") (pin "34") (pinfunction "34_34") (pintype "bidirectional"))
    )
    (net (code "106") (name "B34_L6_P") (class "Default")
      (node (ref "JM1") (pin "32") (pinfunction "32_32") (pintype "bidirectional"))
    )
    (net (code "107") (name "B34_L7_N") (class "Default")
      (node (ref "JM1") (pin "38") (pinfunction "38_38") (pintype "bidirectional"))
      (node (ref "U4") (pin "18") (pinfunction "GPIO1_18") (pintype "bidirectional"))
    )
    (net (code "108") (name "B34_L7_P") (class "Default")
      (node (ref "JM1") (pin "36") (pinfunction "36_36") (pintype "bidirectional"))
    )
    (net (code "109") (name "B34_L8_N") (class "Default")
      (node (ref "JM1") (pin "52") (pinfunction "52_52") (pintype "bidirectional"))
      (node (ref "U3") (pin "13") (pinfunction "SCLK_13") (pintype "input"))
    )
    (net (code "110") (name "B34_L8_P") (class "Default")
      (node (ref "JM1") (pin "50") (pinfunction "50_50") (pintype "bidirectional"))
      (node (ref "U3") (pin "12") (pinfunction "SDOUT_12") (pintype "output"))
    )
    (net (code "111") (name "B34_L9_N") (class "Default")
      (node (ref "JM1") (pin "46") (pinfunction "46_46") (pintype "bidirectional"))
      (node (ref "U4") (pin "33") (pinfunction "GPIO2_33") (pintype "bidirectional"))
    )
    (net (code "112") (name "B34_L9_P") (class "Default")
      (node (ref "JM1") (pin "44") (pinfunction "44_44") (pintype "bidirectional"))
      (node (ref "U4") (pin "36") (pinfunction "GPIO3_36") (pintype "bidirectional"))
    )
    (net (code "113") (name "B34_L10_N") (class "Default")
      (node (ref "JM1") (pin "51") (pinfunction "51_51") (pintype "bidirectional"))
      (node (ref "U5") (pin "11") (pinfunction "SDIN_11") (pintype "input"))
    )
    (net (code "114") (name "B34_L10_P") (class "Default")
      (node (ref "JM1") (pin "49") (pinfunction "49_49") (pintype "bidirectional"))
      (node (ref "U5") (pin "10") (pinfunction "~{CS}_10") (pintype "input"))
    )
    (net (code "115") (name "B34_L11_N") (class "Default")
      (node (ref "JM1") (pin "53") (pinfunction "53_53") (pintype "bidirectional"))
      (node (ref "U5") (pin "12") (pinfunction "SDOUT_12") (pintype "output"))
    )
    (net (code "116") (name "B34_L11_P") (class "Default")
      (node (ref "JM1") (pin "55") (pinfunction "55_55") (pintype "bidirectional"))
      (node (ref "U5") (pin "17") (pinfunction "GPIO0_17") (pintype "bidirectional"))
    )
    (net (code "117") (name "B34_L12_N") (class "Default")
      (node (ref "JM1") (pin "57") (pinfunction "57_57") (pintype "bidirectional"))
      (node (ref "U5") (pin "18") (pinfunction "GPIO1_18") (pintype "bidirectional"))
    )
    (net (code "118") (name "B34_L12_P") (class "Default")
      (node (ref "JM1") (pin "59") (pinfunction "59_59") (pintype "bidirectional"))
      (node (ref "U5") (pin "13") (pinfunction "SCLK_13") (pintype "input"))
    )
    (net (code "119") (name "B34_L13_N") (class "Default")
      (node (ref "JM1") (pin "56") (pinfunction "56_56") (pintype "bidirectional"))
      (node (ref "U3") (pin "18") (pinfunction "GPIO1_18") (pintype "bidirectional"))
    )
    (net (code "120") (name "B34_L13_P") (class "Default")
      (node (ref "JM1") (pin "54") (pinfunction "54_54") (pintype "bidirectional"))
      (node (ref "U3") (pin "17") (pinfunction "GPIO0_17") (pintype "bidirectional"))
    )
    (net (code "121") (name "B34_L14_N") (class "Default")
      (node (ref "JM1") (pin "60") (pinfunction "60_60") (pintype "bidirectional"))
      (node (ref "U3") (pin "36") (pinfunction "GPIO3_36") (pintype "bidirectional"))
    )
    (net (code "122") (name "B34_L14_P") (class "Default")
      (node (ref "JM1") (pin "58") (pinfunction "58_58") (pintype "bidirectional"))
      (node (ref "U3") (pin "33") (pinfunction "GPIO2_33") (pintype "bidirectional"))
    )
    (net (code "123") (name "B34_L15_N") (class "Default")
      (node (ref "JM1") (pin "62") (pinfunction "62_62") (pintype "bidirectional"))
    )
    (net (code "124") (name "B34_L15_P") (class "Default")
      (node (ref "JM1") (pin "64") (pinfunction "64_64") (pintype "bidirectional"))
    )
    (net (code "125") (name "B34_L16_N") (class "Default")
      (node (ref "JM1") (pin "68") (pinfunction "68_68") (pintype "bidirectional"))
    )
    (net (code "126") (name "B34_L16_P") (class "Default")
      (node (ref "JM1") (pin "70") (pinfunction "70_70") (pintype "bidirectional"))
      (node (ref "U4") (pin "32") (pinfunction "RCLK_32") (pintype "input"))
    )
    (net (code "127") (name "B34_L17_N") (class "Default")
      (node (ref "JM1") (pin "63") (pinfunction "63_63") (pintype "bidirectional"))
      (node (ref "U3") (pin "11") (pinfunction "SDIN_11") (pintype "input"))
    )
    (net (code "128") (name "B34_L17_P") (class "Default")
      (node (ref "JM1") (pin "65") (pinfunction "65_65") (pintype "bidirectional"))
      (node (ref "U3") (pin "10") (pinfunction "~{CS}_10") (pintype "input"))
    )
    (net (code "129") (name "B34_L18_N") (class "Default")
      (node (ref "JM1") (pin "74") (pinfunction "74_74") (pintype "bidirectional"))
    )
    (net (code "130") (name "B34_L18_P") (class "Default")
      (node (ref "JM1") (pin "72") (pinfunction "72_72") (pintype "bidirectional"))
    )
    (net (code "131") (name "B34_L19_N") (class "Default")
      (node (ref "JM1") (pin "71") (pinfunction "71_71") (pintype "bidirectional"))
    )
    (net (code "132") (name "B34_L19_P") (class "Default")
      (node (ref "JM1") (pin "73") (pinfunction "73_73") (pintype "bidirectional"))
      (node (ref "U5") (pin "32") (pinfunction "RCLK_32") (pintype "input"))
    )
    (net (code "133") (name "B34_L20_N") (class "Default")
      (node (ref "JM1") (pin "76") (pinfunction "76_76") (pintype "bidirectional"))
    )
    (net (code "134") (name "B34_L20_P") (class "Default")
      (node (ref "JM1") (pin "78") (pinfunction "78_78") (pintype "bidirectional"))
    )
    (net (code "135") (name "B34_L21_N") (class "Default")
      (node (ref "JM1") (pin "69") (pinfunction "69_69") (pintype "bidirectional"))
      (node (ref "U5") (pin "33") (pinfunction "GPIO2_33") (pintype "bidirectional"))
    )
    (net (code "136") (name "B34_L21_P") (class "Default")
      (node (ref "JM1") (pin "67") (pinfunction "67_67") (pintype "bidirectional"))
      (node (ref "U5") (pin "36") (pinfunction "GPIO3_36") (pintype "bidirectional"))
    )
    (net (code "137") (name "B34_L22_N") (class "Default")
      (node (ref "JM1") (pin "75") (pinfunction "75_75") (pintype "bidirectional"))
    )
    (net (code "138") (name "B34_L22_P") (class "Default")
      (node (ref "JM1") (pin "77") (pinfunction "77_77") (pintype "bidirectional"))
    )
    (net (code "139") (name "B34_L23_N") (class "Default")
      (node (ref "JM1") (pin "79") (pinfunction "79_79") (pintype "bidirectional"))
    )
    (net (code "140") (name "B34_L23_P") (class "Default")
      (node (ref "JM1") (pin "81") (pinfunction "81_81") (pintype "bidirectional"))
    )
    (net (code "141") (name "B34_L24_N") (class "Default")
      (node (ref "JM1") (pin "80") (pinfunction "80_80") (pintype "bidirectional"))
    )
    (net (code "142") (name "B34_L24_P") (class "Default")
      (node (ref "JM1") (pin "82") (pinfunction "82_82") (pintype "bidirectional"))
    )
    (net (code "143") (name "BOOTMODE") (class "Default")
      (node (ref "JM2") (pin "100") (pinfunction "100_100") (pintype "bidirectional"))
    )
    (net (code "144") (name "DONE") (class "Default")
      (node (ref "D5") (pin "A") (pinfunction "A_A") (pintype "passive"))
      (node (ref "JM1") (pin "96") (pinfunction "96_96") (pintype "bidirectional"))
      (node (ref "R4") (pin "1") (pinfunction "1_1") (pintype "passive"))
    )
    (net (code "145") (name "EN_A") (class "Default")
      (node (ref "R18") (pin "1") (pinfunction "1_1") (pintype "passive"))
      (node (ref "U6") (pin "1") (pinfunction "EN_1") (pintype "input"))
    )
    (net (code "146") (name "EN_B") (class "Default")
      (node (ref "R21") (pin "1") (pinfunction "1_1") (pintype "passive"))
      (node (ref "U7") (pin "1") (pinfunction "EN_1") (pintype "input"))
    )
    (net (code "147") (name "GND") (class "Default")
      (node (ref "C1") (pin "2") (pinfunction "2_2") (pintype "passive"))
      (node (ref "C10") (pin "2") (pinfunction "2_2") (pintype "passive"))
      (node (ref "C11") (pin "2") (pinfunction "2_2") (pintype "passive"))
      (node (ref "C12") (pin "2") (pinfunction "2_2") (pintype "passive"))
      (node (ref "C13") (pin "2") (pinfunction "2_2") (pintype "passive"))
      (node (ref "C14") (pin "2") (pinfunction "2_2") (pintype "passive"))
      (node (ref "C15") (pin "2") (pinfunction "2_2") (pintype "passive"))
      (node (ref "C16") (pin "2") (pinfunction "2_2") (pintype "passive"))
      (node (ref "C17") (pin "2") (pinfunction "2_2") (pintype "passive"))
      (node (ref "C18") (pin "2") (pinfunction "2_2") (pintype "passive"))
      (node (ref "C19") (pin "2") (pinfunction "2_2") (pintype "passive"))
      (node (ref "C25") (pin "2") (pinfunction "2_2") (pintype "passive"))
      (node (ref "C26") (pin "2") (pinfunction "2_2") (pintype "passive"))
      (node (ref "C27") (pin "2") (pinfunction "2_2") (pintype "passive"))
      (node (ref "C28") (pin "2") (pinfunction "2_2") (pintype "passive"))
      (node (ref "C29") (pin "2") (pinfunction "2_2") (pintype "passive"))
      (node (ref "C30") (pin "2") (pinfunction "2_2") (pintype "passive"))
      (node (ref "C31") (pin "2") (pinfunction "2_2") (pintype "passive"))
      (node (ref "C32") (pin "2") (pinfunction "2_2") (pintype "passive"))
      (node (ref "C33") (pin "2") (pinfunction "2_2") (pintype "passive"))
      (node (ref "C34") (pin "2") (pinfunction "2_2") (pintype "passive"))
      (node (ref "C35") (pin "2") (pinfunction "2_2") (pintype "passive"))
      (node (ref "C36") (pin "2") (pinfunction "2_2") (pintype "passive"))
      (node (ref "C37") (pin "2") (pinfunction "2_2") (pintype "passive"))
      (node (ref "C4") (pin "2") (pinfunction "2_2") (pintype "passive"))
      (node (ref "C43") (pin "2") (pinfunction "2_2") (pintype "passive"))
      (node (ref "C44") (pin "2") (pinfunction "2_2") (pintype "passive"))
      (node (ref "C45") (pin "2") (pinfunction "2_2") (pintype "passive"))
      (node (ref "C46") (pin "2") (pinfunction "2_2") (pintype "passive"))
      (node (ref "C47") (pin "2") (pinfunction "2_2") (pintype "passive"))
      (node (ref "C48") (pin "2") (pinfunction "2_2") (pintype "passive"))
      (node (ref "C49") (pin "2") (pinfunction "2_2") (pintype "passive"))
      (node (ref "C50") (pin "2") (pinfunction "2_2") (pintype "passive"))
      (node (ref "C51") (pin "2") (pinfunction "2_2") (pintype "passive"))
      (node (ref "C52") (pin "2") (pinfunction "2_2") (pintype "passive"))
      (node (ref "C53") (pin "2") (pinfunction "2_2") (pintype "passive"))
      (node (ref "C54") (pin "2") (pinfunction "2_2") (pintype "passive"))
      (node (ref "C55") (pin "2") (pinfunction "2_2") (pintype "passive"))
      (node (ref "C56") (pin "2") (pinfunction "2_2") (pintype "passive"))
      (node (ref "C57") (pin "2") (pinfunction "2_2") (pintype "passive"))
      (node (ref "C58") (pin "2") (pinfunction "2_2") (pintype "passive"))
      (node (ref "C59") (pin "2") (pinfunction "2_2") (pintype "passive"))
      (node (ref "C8") (pin "2") (pinfunction "2_2") (pintype "passive"))
      (node (ref "C9") (pin "2") (pinfunction "2_2") (pintype "passive"))
      (node (ref "D5") (pin "C") (pinfunction "C_C") (pintype "passive"))
      (node (ref "JM1") (pin "100") (pinfunction "100_100") (pintype "bidirectional"))
      (node (ref "JM1") (pin "11") (pinfunction "11_11") (pintype "bidirectional"))
      (node (ref "JM1") (pin "12") (pinfunction "12_12") (pintype "bidirectional"))
      (node (ref "JM1") (pin "17") (pinfunction "17_17") (pintype "bidirectional"))
      (node (ref "JM1") (pin "18") (pinfunction "18_18") (pintype "bidirectional"))
      (node (ref "JM1") (pin "23") (pinfunction "23_23") (pintype "bidirectional"))
      (node (ref "JM1") (pin "24") (pinfunction "24_24") (pintype "bidirectional"))
      (node (ref "JM1") (pin "29") (pinfunction "29_29") (pintype "bidirectional"))
      (node (ref "JM1") (pin "30") (pinfunction "30_30") (pintype "bidirectional"))
      (node (ref "JM1") (pin "47") (pinfunction "47_47") (pintype "bidirectional"))
      (node (ref "JM1") (pin "48") (pinfunction "48_48") (pintype "bidirectional"))
      (node (ref "JM1") (pin "5") (pinfunction "5_5") (pintype "bidirectional"))
      (node (ref "JM1") (pin "6") (pinfunction "6_6") (pintype "bidirectional"))
      (node (ref "JM1") (pin "66") (pinfunction "66_66") (pintype "bidirectional"))
      (node (ref "JM1") (pin "84") (pinfunction "84_84") (pintype "bidirectional"))
      (node (ref "JM1") (pin "98") (pinfunction "98_98") (pintype "bidirectional"))
      (node (ref "JM1") (pin "F1") (pinfunction "F1_F1") (pintype "bidirectional"))
      (node (ref "JM1") (pin "F2") (pinfunction "F2_F2") (pintype "bidirectional"))
      (node (ref "JM2") (pin "17") (pinfunction "17_17") (pintype "bidirectional"))
      (node (ref "JM2") (pin "35") (pinfunction "35_35") (pintype "bidirectional"))
      (node (ref "JM2") (pin "36") (pinfunction "36_36") (pintype "bidirectional"))
      (node (ref "JM2") (pin "72") (pinfunction "72_72") (pintype "bidirectional"))
      (node (ref "JM2") (pin "83") (pinfunction "83_83") (pintype "bidirectional"))
      (node (ref "JM2") (pin "90") (pinfunction "90_90") (pintype "bidirectional"))
      (node (ref "JM2") (pin "F1") (pinfunction "F1_F1") (pintype "bidirectional"))
      (node (ref "JM2") (pin "F2") (pinfunction "F2_F2") (pintype "bidirectional"))
      (node (ref "JP1") (pin "3") (pinfunction "3_3") (pintype "passive"))
      (node (ref "JTAG") (pin "1") (pinfunction "1_1") (pintype "passive"))
      (node (ref "JTAG") (pin "11") (pinfunction "11_11") (pintype "passive"))
      (node (ref "JTAG") (pin "13") (pinfunction "13_13") (pintype "passive"))
      (node (ref "JTAG") (pin "3") (pinfunction "3_3") (pintype "passive"))
      (node (ref "JTAG") (pin "5") (pinfunction "5_5") (pintype "passive"))
      (node (ref "JTAG") (pin "7") (pinfunction "7_7") (pintype "passive"))
      (node (ref "JTAG") (pin "9") (pinfunction "9_9") (pintype "passive"))
      (node (ref "OUT1") (pin "2@1") (pinfunction "GND_2@1") (pintype "passive"))
      (node (ref "OUT1") (pin "2@2") (pinfunction "GND_2@2") (pintype "passive"))
      (node (ref "OUT1") (pin "2@3") (pinfunction "GND_2@3") (pintype "passive"))
      (node (ref "OUT2") (pin "2@1") (pinfunction "GND_2@1") (pintype "passive"))
      (node (ref "OUT2") (pin "2@2") (pinfunction "GND_2@2") (pintype "passive"))
      (node (ref "OUT2") (pin "2@3") (pinfunction "GND_2@3") (pintype "passive"))
      (node (ref "PCIE-NORTH") (pin "A1") (pinfunction "GND_A1") (pintype "passive"))
      (node (ref "PCIE-NORTH") (pin "A10") (pinfunction "GND_A10") (pintype "passive"))
      (node (ref "PCIE-NORTH") (pin "A12") (pinfunction "GND_A12") (pintype "passive"))
      (node (ref "PCIE-NORTH") (pin "A15") (pinfunction "GND_A15") (pintype "passive"))
      (node (ref "PCIE-NORTH") (pin "A18") (pinfunction "GND_A18") (pintype "passive"))
      (node (ref "PCIE-NORTH") (pin "A4") (pinfunction "GND_A4") (pintype "passive"))
      (node (ref "PCIE-NORTH") (pin "A7") (pinfunction "GND_A7") (pintype "passive"))
      (node (ref "PCIE-NORTH") (pin "B15") (pinfunction "GND_B15") (pintype "passive"))
      (node (ref "PCIE-NORTH") (pin "B18") (pinfunction "GND_B18") (pintype "passive"))
      (node (ref "PCIE-SOUTH") (pin "A1") (pinfunction "GND_A1") (pintype "passive"))
      (node (ref "PCIE-SOUTH") (pin "A10") (pinfunction "GND_A10") (pintype "passive"))
      (node (ref "PCIE-SOUTH") (pin "A12") (pinfunction "GND_A12") (pintype "passive"))
      (node (ref "PCIE-SOUTH") (pin "A15") (pinfunction "GND_A15") (pintype "passive"))
      (node (ref "PCIE-SOUTH") (pin "A18") (pinfunction "GND_A18") (pintype "passive"))
      (node (ref "PCIE-SOUTH") (pin "A4") (pinfunction "GND_A4") (pintype "passive"))
      (node (ref "PCIE-SOUTH") (pin "A7") (pinfunction "GND_A7") (pintype "passive"))
      (node (ref "PCIE-SOUTH") (pin "B15") (pinfunction "GND_B15") (pintype "passive"))
      (node (ref "PCIE-SOUTH") (pin "B18") (pinfunction "GND_B18") (pintype "passive"))
      (node (ref "R10") (pin "2") (pinfunction "2_2") (pintype "passive"))
      (node (ref "R11") (pin "2") (pinfunction "2_2") (pintype "passive"))
      (node (ref "R12") (pin "2") (pinfunction "2_2") (pintype "passive"))
      (node (ref "R13") (pin "2") (pinfunction "2_2") (pintype "passive"))
      (node (ref "R14") (pin "2") (pinfunction "2_2") (pintype "passive"))
      (node (ref "R15") (pin "2") (pinfunction "2_2") (pintype "passive"))
      (node (ref "R16") (pin "2") (pinfunction "2_2") (pintype "passive"))
      (node (ref "R19") (pin "1") (pinfunction "1_1") (pintype "passive"))
      (node (ref "R22") (pin "1") (pinfunction "1_1") (pintype "passive"))
      (node (ref "R3") (pin "2") (pinfunction "2_2") (pintype "passive"))
      (node (ref "SDI-IN") (pin "2@1") (pinfunction "GND_2@1") (pintype "passive"))
      (node (ref "SDI-IN") (pin "2@2") (pinfunction "GND_2@2") (pintype "passive"))
      (node (ref "SDI-IN") (pin "2@3") (pinfunction "GND_2@3") (pintype "passive"))
      (node (ref "U1") (pin "3") (pinfunction "GND_3") (pintype "passive"))
      (node (ref "U2") (pin "1") (pinfunction "A0_1") (pintype "input"))
      (node (ref "U2") (pin "2") (pinfunction "A1_2") (pintype "input"))
      (node (ref "U2") (pin "3") (pinfunction "A2_3") (pintype "input"))
      (node (ref "U2") (pin "4") (pinfunction "GND_4") (pintype "passive"))
      (node (ref "U2") (pin "EP") (pinfunction "EP_EP") (pintype "passive"))
      (node (ref "U3") (pin "1") (pinfunction "VEE_SDI_1") (pintype "power_in"))
      (node (ref "U3") (pin "14") (pinfunction "VSS_14") (pintype "power_in"))
      (node (ref "U3") (pin "15") (pinfunction "VSS_15") (pintype "power_in"))
      (node (ref "U3") (pin "19") (pinfunction "VEE_CORE_19") (pintype "power_in"))
      (node (ref "U3") (pin "21") (pinfunction "VEEO_21") (pintype "power_in"))
      (node (ref "U3") (pin "28") (pinfunction "VEEO_28") (pintype "power_in"))
      (node (ref "U3") (pin "31") (pinfunction "VEE_CORE_31") (pintype "power_in"))
      (node (ref "U3") (pin "37") (pinfunction "VEE_CORE_37") (pintype "power_in"))
      (node (ref "U3") (pin "38") (pinfunction "VEE_CORE_38") (pintype "power_in"))
      (node (ref "U3") (pin "8") (pinfunction "VEE_SDI_8") (pintype "power_in"))
      (node (ref "U4") (pin "1") (pinfunction "VEE_DDI_1") (pintype "power_in"))
      (node (ref "U4") (pin "14") (pinfunction "VSS_14") (pintype "power_in"))
      (node (ref "U4") (pin "15") (pinfunction "VSS_15") (pintype "power_in"))
      (node (ref "U4") (pin "19") (pinfunction "VEE_CORE_19") (pintype "power_in"))
      (node (ref "U4") (pin "21") (pinfunction "VEEO_21") (pintype "power_in"))
      (node (ref "U4") (pin "28") (pinfunction "VEEO_28") (pintype "power_in"))
      (node (ref "U4") (pin "31") (pinfunction "VEE_CORE_31") (pintype "power_in"))
      (node (ref "U4") (pin "37") (pinfunction "VEE_CORE_37") (pintype "power_in"))
      (node (ref "U4") (pin "38") (pinfunction "VEE_CORE_38") (pintype "power_in"))
      (node (ref "U4") (pin "8") (pinfunction "VEE_DDI_8") (pintype "power_in"))
      (node (ref "U5") (pin "1") (pinfunction "VEE_DDI_1") (pintype "power_in"))
      (node (ref "U5") (pin "14") (pinfunction "VSS_14") (pintype "power_in"))
      (node (ref "U5") (pin "15") (pinfunction "VSS_15") (pintype "power_in"))
      (node (ref "U5") (pin "19") (pinfunction "VEE_CORE_19") (pintype "power_in"))
      (node (ref "U5") (pin "21") (pinfunction "VEEO_21") (pintype "power_in"))
      (node (ref "U5") (pin "28") (pinfunction "VEEO_28") (pintype "power_in"))
      (node (ref "U5") (pin "31") (pinfunction "VEE_CORE_31") (pintype "power_in"))
      (node (ref "U5") (pin "37") (pinfunction "VEE_CORE_37") (pintype "power_in"))
      (node (ref "U5") (pin "38") (pinfunction "VEE_CORE_38") (pintype "power_in"))
      (node (ref "U5") (pin "8") (pinfunction "VEE_DDI_8") (pintype "power_in"))
      (node (ref "U6") (pin "5") (pinfunction "GND_5") (pintype "passive"))
      (node (ref "U6") (pin "6") (pinfunction "GND_6") (pintype "passive"))
      (node (ref "U6") (pin "EP") (pinfunction "GND_EP") (pintype "passive"))
      (node (ref "U7") (pin "5") (pinfunction "GND_5") (pintype "passive"))
      (node (ref "U7") (pin "6") (pinfunction "GND_6") (pintype "passive"))
      (node (ref "U7") (pin "EP") (pinfunction "GND_EP") (pintype "passive"))
    )
    (net (code "148") (name "I2C_V") (class "Default")
      (node (ref "C4") (pin "1") (pinfunction "1_1") (pintype "passive"))
      (node (ref "PCIE-NORTH") (pin "B3") (pinfunction "V_I2C_B3") (pintype "passive"))
      (node (ref "R2") (pin "1") (pinfunction "1_1") (pintype "passive"))
      (node (ref "U2") (pin "8") (pinfunction "VCC_8") (pintype "power_in"))
    )
    (net (code "149") (name "MGT_CLK0_N") (class "Default")
      (node (ref "C3") (pin "2") (pinfunction "2_2") (pintype "passive"))
      (node (ref "JM1") (pin "4") (pinfunction "4_4") (pintype "bidirectional"))
    )
    (net (code "150") (name "MGT_CLK0_P") (class "Default")
      (node (ref "C2") (pin "2") (pinfunction "2_2") (pintype "passive"))
      (node (ref "JM1") (pin "2") (pinfunction "2_2") (pintype "bidirectional"))
    )
    (net (code "151") (name "MGT_RX0_N") (class "Default")
      (node (ref "JM1") (pin "21") (pinfunction "21_21") (pintype "bidirectional"))
      (node (ref "U3") (pin "27") (pinfunction "DDO0_27") (pintype "output"))
    )
    (net (code "152") (name "MGT_RX0_P") (class "Default")
      (node (ref "JM1") (pin "19") (pinfunction "19_19") (pintype "bidirectional"))
      (node (ref "U3") (pin "26") (pinfunction "~{DDO0}_26") (pintype "output"))
    )
    (net (code "153") (name "MGT_RX1_N") (class "Default")
      (node (ref "JM1") (pin "15") (pinfunction "15_15") (pintype "bidirectional"))
      (node (ref "U3") (pin "23") (pinfunction "DDO1/RCO_23") (pintype "output"))
    )
    (net (code "154") (name "MGT_RX1_P") (class "Default")
      (node (ref "JM1") (pin "13") (pinfunction "13_13") (pintype "bidirectional"))
      (node (ref "U3") (pin "22") (pinfunction "~{DDO1}/~{RCO}_22") (pintype "output"))
    )
    (net (code "155") (name "MGT_RX2_N") (class "Default")
      (node (ref "JM1") (pin "9") (pinfunction "9_9") (pintype "bidirectional"))
    )
    (net (code "156") (name "MGT_RX2_P") (class "Default")
      (node (ref "JM1") (pin "7") (pinfunction "7_7") (pintype "bidirectional"))
    )
    (net (code "157") (name "MGT_RX3_N") (class "Default")
      (node (ref "JM1") (pin "3") (pinfunction "3_3") (pintype "bidirectional"))
    )
    (net (code "158") (name "MGT_RX3_P") (class "Default")
      (node (ref "JM1") (pin "1") (pinfunction "1_1") (pintype "bidirectional"))
    )
    (net (code "159") (name "MGT_TX0_N") (class "Default")
      (node (ref "JM1") (pin "28") (pinfunction "28_28") (pintype "bidirectional"))
      (node (ref "U5") (pin "6") (pinfunction "DDI_6") (pintype "input"))
    )
    (net (code "160") (name "MGT_TX0_P") (class "Default")
      (node (ref "JM1") (pin "26") (pinfunction "26_26") (pintype "bidirectional"))
      (node (ref "U5") (pin "7") (pinfunction "~{DDI}_7") (pintype "input"))
    )
    (net (code "161") (name "MGT_TX1_N") (class "Default")
      (node (ref "JM1") (pin "22") (pinfunction "22_22") (pintype "bidirectional"))
      (node (ref "U4") (pin "6") (pinfunction "DDI_6") (pintype "input"))
    )
    (net (code "162") (name "MGT_TX1_P") (class "Default")
      (node (ref "JM1") (pin "20") (pinfunction "20_20") (pintype "bidirectional"))
      (node (ref "U4") (pin "7") (pinfunction "~{DDI}_7") (pintype "input"))
    )
    (net (code "163") (name "MGT_TX2_N") (class "Default")
      (node (ref "JM1") (pin "16") (pinfunction "16_16") (pintype "bidirectional"))
    )
    (net (code "164") (name "MGT_TX2_P") (class "Default")
      (node (ref "JM1") (pin "14") (pinfunction "14_14") (pintype "bidirectional"))
    )
    (net (code "165") (name "MGT_TX3_N") (class "Default")
      (node (ref "JM1") (pin "10") (pinfunction "10_10") (pintype "bidirectional"))
    )
    (net (code "166") (name "MGT_TX3_P") (class "Default")
      (node (ref "JM1") (pin "8") (pinfunction "8_8") (pintype "bidirectional"))
    )
    (net (code "167") (name "M_1V8") (class "Default")
      (node (ref "JM2") (pin "18") (pinfunction "18_18") (pintype "bidirectional"))
      (node (ref "R5") (pin "2") (pinfunction "2_2") (pintype "passive"))
    )
    (net (code "168") (name "N_5V") (class "Default")
      (node (ref "PCIE-NORTH") (pin "B12") (pinfunction "5V_B12") (pintype "passive"))
    )
    (net (code "169") (name "N_IO0") (class "Default")
      (node (ref "PCIE-NORTH") (pin "B4") (pinfunction "IO0_B4") (pintype "passive"))
    )
    (net (code "170") (name "N_IO1") (class "Default")
      (node (ref "PCIE-NORTH") (pin "B5") (pinfunction "IO1_B5") (pintype "passive"))
    )
    (net (code "171") (name "N_IO2") (class "Default")
      (node (ref "PCIE-NORTH") (pin "B6") (pinfunction "IO2_B6") (pintype "passive"))
    )
    (net (code "172") (name "N_IO3") (class "Default")
      (node (ref "PCIE-NORTH") (pin "B7") (pinfunction "IO3_B7") (pintype "passive"))
    )
    (net (code "173") (name "N_IO4") (class "Default")
      (node (ref "PCIE-NORTH") (pin "B8") (pinfunction "IO4_B8") (pintype "passive"))
    )
    (net (code "174") (name "N_IO5") (class "Default")
      (node (ref "PCIE-NORTH") (pin "B9") (pinfunction "IO5_B9") (pintype "passive"))
    )
    (net (code "175") (name "N_IO6") (class "Default")
      (node (ref "PCIE-NORTH") (pin "B10") (pinfunction "IO6_B10") (pintype "passive"))
    )
    (net (code "176") (name "N_IO7") (class "Default")
      (node (ref "PCIE-NORTH") (pin "B11") (pinfunction "IO7_B11") (pintype "passive"))
    )
    (net (code "177") (name "N_PCIE_V") (class "Default")
      (node (ref "PCIE-NORTH") (pin "B13") (pinfunction "VCC_B13") (pintype "passive"))
    )
    (net (code "178") (name "N_VCCIO") (class "Default")
      (node (ref "PCIE-NORTH") (pin "B14") (pinfunction "VCCIO_B14") (pintype "passive"))
    )
    (net (code "179") (name "Net-(C5-Pad1)") (class "Default")
      (node (ref "C5") (pin "1") (pinfunction "1_1") (pintype "passive"))
      (node (ref "SDI-IN") (pin "1") (pinfunction "1_1") (pintype "passive"))
    )
    (net (code "180") (name "Net-(C7-Pad2)") (class "Default")
      (node (ref "C7") (pin "2") (pinfunction "2_2") (pintype "passive"))
      (node (ref "R10") (pin "1") (pinfunction "1_1") (pintype "passive"))
    )
    (net (code "181") (name "Net-(C20-Pad2)") (class "Default")
      (node (ref "C20") (pin "2") (pinfunction "2_2") (pintype "passive"))
      (node (ref "OUT1") (pin "1") (pinfunction "1_1") (pintype "passive"))
    )
    (net (code "182") (name "Net-(C21-Pad2)") (class "Default")
      (node (ref "C21") (pin "2") (pinfunction "2_2") (pintype "passive"))
      (node (ref "R11") (pin "1") (pinfunction "1_1") (pintype "passive"))
    )
    (net (code "183") (name "Net-(C22-Pad2)") (class "Default")
      (node (ref "C22") (pin "2") (pinfunction "2_2") (pintype "passive"))
      (node (ref "R12") (pin "1") (pinfunction "1_1") (pintype "passive"))
    )
    (net (code "184") (name "Net-(C23-Pad2)") (class "Default")
      (node (ref "C23") (pin "2") (pinfunction "2_2") (pintype "passive"))
      (node (ref "R13") (pin "1") (pinfunction "1_1") (pintype "passive"))
    )
    (net (code "185") (name "Net-(C38-Pad2)") (class "Default")
      (node (ref "C38") (pin "2") (pinfunction "2_2") (pintype "passive"))
      (node (ref "OUT2") (pin "1") (pinfunction "1_1") (pintype "passive"))
    )
    (net (code "186") (name "Net-(C39-Pad2)") (class "Default")
      (node (ref "C39") (pin "2") (pinfunction "2_2") (pintype "passive"))
      (node (ref "R14") (pin "1") (pinfunction "1_1") (pintype "passive"))
    )
    (net (code "187") (name "Net-(C40-Pad2)") (class "Default")
      (node (ref "C40") (pin "2") (pinfunction "2_2") (pintype "passive"))
      (node (ref "R15") (pin "1") (pinfunction "1_1") (pintype "passive"))
    )
    (net (code "188") (name "Net-(C41-Pad2)") (class "Default")
      (node (ref "C41") (pin "2") (pinfunction "2_2") (pintype "passive"))
      (node (ref "R16") (pin "1") (pinfunction "1_1") (pintype "passive"))
    )
    (net (code "189") (name "Net-(D1-PadC)") (class "Default")
      (node (ref "D1") (pin "C") (pinfunction "C_C") (pintype "passive"))
      (node (ref "R6") (pin "2") (pinfunction "2_2") (pintype "passive"))
    )
    (net (code "190") (name "Net-(D2-PadC)") (class "Default")
      (node (ref "D2") (pin "C") (pinfunction "C_C") (pintype "passive"))
      (node (ref "R7") (pin "2") (pinfunction "2_2") (pintype "passive"))
    )
    (net (code "191") (name "Net-(D3-PadC)") (class "Default")
      (node (ref "D3") (pin "C") (pinfunction "C_C") (pintype "passive"))
      (node (ref "R8") (pin "2") (pinfunction "2_2") (pintype "passive"))
    )
    (net (code "192") (name "Net-(D4-PadC)") (class "Default")
      (node (ref "D4") (pin "C") (pinfunction "C_C") (pintype "passive"))
      (node (ref "R9") (pin "2") (pinfunction "2_2") (pintype "passive"))
    )
    (net (code "193") (name "Net-(U1-OUT+)") (class "Default")
      (node (ref "C2") (pin "1") (pinfunction "1_1") (pintype "passive"))
      (node (ref "R1") (pin "1") (pinfunction "1_1") (pintype "passive"))
      (node (ref "U1") (pin "4") (pinfunction "OUT+_4") (pintype "output"))
    )
    (net (code "194") (name "Net-(U1-OUT-)") (class "Default")
      (node (ref "C3") (pin "1") (pinfunction "1_1") (pintype "passive"))
      (node (ref "R1") (pin "2") (pinfunction "2_2") (pintype "passive"))
      (node (ref "U1") (pin "5") (pinfunction "OUT-_5") (pintype "output"))
    )
    (net (code "195") (name "Net-(U2-WP)") (class "Default")
      (node (ref "R2") (pin "2") (pinfunction "2_2") (pintype "passive"))
      (node (ref "R3") (pin "1") (pinfunction "1_1") (pintype "passive"))
      (node (ref "U2") (pin "7") (pinfunction "WP_7") (pintype "input"))
    )
    (net (code "196") (name "Net-(U3-LF+)") (class "Default")
      (node (ref "C6") (pin "1") (pinfunction "1_1") (pintype "passive"))
      (node (ref "U3") (pin "39") (pinfunction "LF+_39") (pintype "passive"))
    )
    (net (code "197") (name "Net-(U3-LF-)") (class "Default")
      (node (ref "C6") (pin "2") (pinfunction "2_2") (pintype "passive"))
      (node (ref "U3") (pin "40") (pinfunction "LF-_40") (pintype "passive"))
    )
    (net (code "198") (name "Net-(U3-SDI)") (class "Default")
      (node (ref "C5") (pin "2") (pinfunction "2_2") (pintype "passive"))
      (node (ref "U3") (pin "2") (pinfunction "SDI_2") (pintype "input"))
    )
    (net (code "199") (name "Net-(U3-SDI_TERM)") (class "Default")
      (node (ref "C7") (pin "1") (pinfunction "1_1") (pintype "passive"))
      (node (ref "U3") (pin "3") (pinfunction "SDI_TERM_3") (pintype "passive"))
    )
    (net (code "200") (name "Net-(U3-VCO_FILT)") (class "Default")
      (node (ref "C8") (pin "1") (pinfunction "1_1") (pintype "passive"))
      (node (ref "U3") (pin "34") (pinfunction "VCO_FILT_34") (pintype "passive"))
    )
    (net (code "201") (name "Net-(U3-VCO_FILT10)") (class "Default")
      (node (ref "C9") (pin "1") (pinfunction "1_1") (pintype "passive"))
      (node (ref "U3") (pin "30") (pinfunction "VCO_FILT10_30") (pintype "passive"))
    )
    (net (code "202") (name "Net-(U4-LF+)") (class "Default")
      (node (ref "C24") (pin "1") (pinfunction "1_1") (pintype "passive"))
      (node (ref "U4") (pin "39") (pinfunction "LF+_39") (pintype "passive"))
    )
    (net (code "203") (name "Net-(U4-LF-)") (class "Default")
      (node (ref "C24") (pin "2") (pinfunction "2_2") (pintype "passive"))
      (node (ref "U4") (pin "40") (pinfunction "LF-_40") (pintype "passive"))
    )
    (net (code "204") (name "Net-(U4-SDO0)") (class "Default")
      (node (ref "C20") (pin "1") (pinfunction "1_1") (pintype "passive"))
      (node (ref "U4") (pin "27") (pinfunction "SDO0_27") (pintype "output"))
    )
    (net (code "205") (name "Net-(U4-SDO1{slash}RCO)") (class "Default")
      (node (ref "C22") (pin "1") (pinfunction "1_1") (pintype "passive"))
      (node (ref "U4") (pin "23") (pinfunction "SDO1/RCO_23") (pintype "output"))
    )
    (net (code "206") (name "Net-(U4-TERM)") (class "Default")
      (node (ref "C25") (pin "1") (pinfunction "1_1") (pintype "passive"))
      (node (ref "U4") (pin "5") (pinfunction "TERM_5") (pintype "passive"))
    )
    (net (code "207") (name "Net-(U4-VCO_FILT)") (class "Default")
      (node (ref "C26") (pin "1") (pinfunction "1_1") (pintype "passive"))
      (node (ref "U4") (pin "34") (pinfunction "VCO_FILT_34") (pintype "passive"))
    )
    (net (code "208") (name "Net-(U4-VCO_FILT10)") (class "Default")
      (node (ref "C27") (pin "1") (pinfunction "1_1") (pintype "passive"))
      (node (ref "U4") (pin "30") (pinfunction "VCO_FILT10_30") (pintype "passive"))
    )
    (net (code "209") (name "Net-(U4-~{SDO0})") (class "Default")
      (node (ref "C23") (pin "1") (pinfunction "1_1") (pintype "passive"))
      (node (ref "U4") (pin "26") (pinfunction "~{SDO0}_26") (pintype "output"))
    )
    (net (code "210") (name "Net-(U4-~{SDO1}{slash}~{RCO})") (class "Default")
      (node (ref "C21") (pin "1") (pinfunction "1_1") (pintype "passive"))
      (node (ref "U4") (pin "22") (pinfunction "~{SDO1}/~{RCO}_22") (pintype "output"))
    )
    (net (code "211") (name "Net-(U5-LF+)") (class "Default")
      (node (ref "C42") (pin "1") (pinfunction "1_1") (pintype "passive"))
      (node (ref "U5") (pin "39") (pinfunction "LF+_39") (pintype "passive"))
    )
    (net (code "212") (name "Net-(U5-LF-)") (class "Default")
      (node (ref "C42") (pin "2") (pinfunction "2_2") (pintype "passive"))
      (node (ref "U5") (pin "40") (pinfunction "LF-_40") (pintype "passive"))
    )
    (net (code "213") (name "Net-(U5-SDO0)") (class "Default")
      (node (ref "C41") (pin "1") (pinfunction "1_1") (pintype "passive"))
      (node (ref "U5") (pin "27") (pinfunction "SDO0_27") (pintype "output"))
    )
    (net (code "214") (name "Net-(U5-SDO1{slash}RCO)") (class "Default")
      (node (ref "C38") (pin "1") (pinfunction "1_1") (pintype "passive"))
      (node (ref "U5") (pin "23") (pinfunction "SDO1/RCO_23") (pintype "output"))
    )
    (net (code "215") (name "Net-(U5-TERM)") (class "Default")
      (node (ref "C43") (pin "1") (pinfunction "1_1") (pintype "passive"))
      (node (ref "U5") (pin "5") (pinfunction "TERM_5") (pintype "passive"))
    )
    (net (code "216") (name "Net-(U5-VCO_FILT)") (class "Default")
      (node (ref "C44") (pin "1") (pinfunction "1_1") (pintype "passive"))
      (node (ref "U5") (pin "34") (pinfunction "VCO_FILT_34") (pintype "passive"))
    )
    (net (code "217") (name "Net-(U5-VCO_FILT10)") (class "Default")
      (node (ref "C45") (pin "1") (pinfunction "1_1") (pintype "passive"))
      (node (ref "U5") (pin "30") (pinfunction "VCO_FILT10_30") (pintype "passive"))
    )
    (net (code "218") (name "Net-(U5-~{SDO0})") (class "Default")
      (node (ref "C40") (pin "1") (pinfunction "1_1") (pintype "passive"))
      (node (ref "U5") (pin "26") (pinfunction "~{SDO0}_26") (pintype "output"))
    )
    (net (code "219") (name "Net-(U5-~{SDO1}{slash}~{RCO})") (class "Default")
      (node (ref "C39") (pin "1") (pinfunction "1_1") (pintype "passive"))
      (node (ref "U5") (pin "22") (pinfunction "~{SDO1}/~{RCO}_22") (pintype "output"))
    )
    (net (code "220") (name "Net-(U6-FB)") (class "Default")
      (node (ref "R17") (pin "1") (pinfunction "1_1") (pintype "passive"))
      (node (ref "R19") (pin "2") (pinfunction "2_2") (pintype "passive"))
      (node (ref "U6") (pin "7") (pinfunction "FB_7") (pintype "output"))
    )
    (net (code "221") (name "Net-(U7-FB)") (class "Default")
      (node (ref "R20") (pin "1") (pinfunction "1_1") (pintype "passive"))
      (node (ref "R22") (pin "2") (pinfunction "2_2") (pintype "passive"))
      (node (ref "U7") (pin "7") (pinfunction "FB_7") (pintype "output"))
    )
    (net (code "222") (name "PROG_B") (class "Default")
      (node (ref "JM1") (pin "94") (pinfunction "94_94") (pintype "bidirectional"))
    )
    (net (code "223") (name "SCL") (class "Default")
      (node (ref "PCIE-NORTH") (pin "B2") (pinfunction "SCL_B2") (pintype "passive"))
      (node (ref "U2") (pin "6") (pinfunction "SCL_6") (pintype "input"))
    )
    (net (code "224") (name "SDA") (class "Default")
      (node (ref "PCIE-NORTH") (pin "B1") (pinfunction "SDA_B1") (pintype "passive"))
      (node (ref "U2") (pin "5") (pinfunction "SDA_5") (pintype "bidirectional"))
    )
    (net (code "225") (name "SPI-CLK") (class "Default")
      (node (ref "JM2") (pin "67") (pinfunction "67_67") (pintype "bidirectional"))
    )
    (net (code "226") (name "SPI-CS") (class "Default")
      (node (ref "JM2") (pin "69") (pinfunction "69_69") (pintype "bidirectional"))
    )
    (net (code "227") (name "SPI-DQ0") (class "Default")
      (node (ref "JM2") (pin "68") (pinfunction "68_68") (pintype "bidirectional"))
    )
    (net (code "228") (name "SPI-DQ1") (class "Default")
      (node (ref "JM2") (pin "71") (pinfunction "71_71") (pintype "bidirectional"))
    )
    (net (code "229") (name "SPI-DQ2") (class "Default")
      (node (ref "JM2") (pin "73") (pinfunction "73_73") (pintype "bidirectional"))
    )
    (net (code "230") (name "SPI-DQ3") (class "Default")
      (node (ref "JM2") (pin "70") (pinfunction "70_70") (pintype "bidirectional"))
    )
    (net (code "231") (name "S_5V") (class "Default")
      (node (ref "JP1") (pin "1") (pinfunction "1_1") (pintype "passive"))
      (node (ref "PCIE-SOUTH") (pin "B12") (pinfunction "5V_B12") (pintype "passive"))
    )
    (net (code "232") (name "S_PCIE_V") (class "Default")
      (node (ref "PCIE-SOUTH") (pin "B13") (pinfunction "VCC_B13") (pintype "passive"))
    )
    (net (code "233") (name "S_VCCIO") (class "Default")
      (node (ref "JM2") (pin "54") (pinfunction "54_54") (pintype "bidirectional"))
      (node (ref "PCIE-SOUTH") (pin "B14") (pinfunction "VCCIO_B14") (pintype "passive"))
    )
    (net (code "234") (name "TCK") (class "Default")
      (node (ref "JM1") (pin "90") (pinfunction "90_90") (pintype "bidirectional"))
      (node (ref "JTAG") (pin "6") (pinfunction "6_6") (pintype "passive"))
    )
    (net (code "235") (name "TDI") (class "Default")
      (node (ref "JM1") (pin "86") (pinfunction "86_86") (pintype "bidirectional"))
      (node (ref "JTAG") (pin "10") (pinfunction "10_10") (pintype "passive"))
    )
    (net (code "236") (name "TDO") (class "Default")
      (node (ref "JM1") (pin "88") (pinfunction "88_88") (pintype "bidirectional"))
      (node (ref "JTAG") (pin "8") (pinfunction "8_8") (pintype "passive"))
    )
    (net (code "237") (name "TMS") (class "Default")
      (node (ref "JM1") (pin "92") (pinfunction "92_92") (pintype "bidirectional"))
      (node (ref "JTAG") (pin "4") (pinfunction "4_4") (pintype "passive"))
    )
    (net (code "238") (name "VCCIO0") (class "Default")
      (node (ref "JM2") (pin "53") (pinfunction "53_53") (pintype "bidirectional"))
      (node (ref "JTAG") (pin "2") (pinfunction "2_2") (pintype "passive"))
    )
    (net (code "239") (name "VCCIO14") (class "Default")
      (node (ref "JM1") (pin "83") (pinfunction "83_83") (pintype "bidirectional"))
    )
    (net (code "240") (name "VCCO_4") (class "Default")
      (node (ref "C17") (pin "1") (pinfunction "1_1") (pintype "passive"))
      (node (ref "C18") (pin "1") (pinfunction "1_1") (pintype "passive"))
      (node (ref "C19") (pin "1") (pinfunction "1_1") (pintype "passive"))
      (node (ref "FB4") (pin "2") (pinfunction "2_2") (pintype "passive"))
      (node (ref "U3") (pin "24") (pinfunction "VCCO_1_24") (pintype "power_in"))
      (node (ref "U3") (pin "25") (pinfunction "VCCO_0_25") (pintype "power_in"))
    )
    (net (code "241") (name "VCCO_8") (class "Default")
      (node (ref "C35") (pin "1") (pinfunction "1_1") (pintype "passive"))
      (node (ref "C36") (pin "1") (pinfunction "1_1") (pintype "passive"))
      (node (ref "C37") (pin "1") (pinfunction "1_1") (pintype "passive"))
      (node (ref "FB7") (pin "2") (pinfunction "2_2") (pintype "passive"))
      (node (ref "U4") (pin "24") (pinfunction "VCCO_1_24") (pintype "power_in"))
      (node (ref "U4") (pin "25") (pinfunction "VCCO_0_25") (pintype "power_in"))
    )
    (net (code "242") (name "VCCO_9") (class "Default")
      (node (ref "C53") (pin "1") (pinfunction "1_1") (pintype "passive"))
      (node (ref "C54") (pin "1") (pinfunction "1_1") (pintype "passive"))
      (node (ref "C55") (pin "1") (pinfunction "1_1") (pintype "passive"))
      (node (ref "FB10") (pin "2") (pinfunction "2_2") (pintype "passive"))
      (node (ref "U5") (pin "24") (pinfunction "VCCO_1_24") (pintype "power_in"))
      (node (ref "U5") (pin "25") (pinfunction "VCCO_0_25") (pintype "power_in"))
    )
    (net (code "243") (name "VCC_4") (class "Default")
      (node (ref "C14") (pin "1") (pinfunction "1_1") (pintype "passive"))
      (node (ref "C15") (pin "1") (pinfunction "1_1") (pintype "passive"))
      (node (ref "C16") (pin "1") (pinfunction "1_1") (pintype "passive"))
      (node (ref "FB3") (pin "2") (pinfunction "2_2") (pintype "passive"))
      (node (ref "U3") (pin "35") (pinfunction "VCC_CORE_35") (pintype "power_in"))
      (node (ref "U3") (pin "4") (pinfunction "VCC_SDI_4") (pintype "power_in"))
    )
    (net (code "244") (name "VCC_8") (class "Default")
      (node (ref "C32") (pin "1") (pinfunction "1_1") (pintype "passive"))
      (node (ref "C33") (pin "1") (pinfunction "1_1") (pintype "passive"))
      (node (ref "C34") (pin "1") (pinfunction "1_1") (pintype "passive"))
      (node (ref "FB6") (pin "2") (pinfunction "2_2") (pintype "passive"))
      (node (ref "U4") (pin "35") (pinfunction "VCC_CORE_35") (pintype "power_in"))
      (node (ref "U4") (pin "4") (pinfunction "VCC_DDI_4") (pintype "power_in"))
    )
    (net (code "245") (name "VCC_9") (class "Default")
      (node (ref "C50") (pin "1") (pinfunction "1_1") (pintype "passive"))
      (node (ref "C51") (pin "1") (pinfunction "1_1") (pintype "passive"))
      (node (ref "C52") (pin "1") (pinfunction "1_1") (pintype "passive"))
      (node (ref "FB9") (pin "2") (pinfunction "2_2") (pintype "passive"))
      (node (ref "U5") (pin "35") (pinfunction "VCC_CORE_35") (pintype "power_in"))
      (node (ref "U5") (pin "4") (pinfunction "VCC_DDI_4") (pintype "power_in"))
    )
    (net (code "246") (name "VDD_4") (class "Default")
      (node (ref "C10") (pin "1") (pinfunction "1_1") (pintype "passive"))
      (node (ref "C11") (pin "1") (pinfunction "1_1") (pintype "passive"))
      (node (ref "C12") (pin "1") (pinfunction "1_1") (pintype "passive"))
      (node (ref "C13") (pin "1") (pinfunction "1_1") (pintype "passive"))
      (node (ref "FB2") (pin "2") (pinfunction "2_2") (pintype "passive"))
      (node (ref "U3") (pin "16") (pinfunction "VDD_16") (pintype "power_in"))
      (node (ref "U3") (pin "20") (pinfunction "VCCO1V8_1_20") (pintype "power_in"))
      (node (ref "U3") (pin "29") (pinfunction "VCCO1V8_0_29") (pintype "power_in"))
    )
    (net (code "247") (name "VDD_8") (class "Default")
      (node (ref "C28") (pin "1") (pinfunction "1_1") (pintype "passive"))
      (node (ref "C29") (pin "1") (pinfunction "1_1") (pintype "passive"))
      (node (ref "C30") (pin "1") (pinfunction "1_1") (pintype "passive"))
      (node (ref "C31") (pin "1") (pinfunction "1_1") (pintype "passive"))
      (node (ref "FB5") (pin "2") (pinfunction "2_2") (pintype "passive"))
      (node (ref "U4") (pin "16") (pinfunction "VDD_16") (pintype "power_in"))
      (node (ref "U4") (pin "20") (pinfunction "VCCO1V8_1_20") (pintype "power_in"))
      (node (ref "U4") (pin "29") (pinfunction "VCCO1V8_0_29") (pintype "power_in"))
    )
    (net (code "248") (name "VDD_9") (class "Default")
      (node (ref "C46") (pin "1") (pinfunction "1_1") (pintype "passive"))
      (node (ref "C47") (pin "1") (pinfunction "1_1") (pintype "passive"))
      (node (ref "C48") (pin "1") (pinfunction "1_1") (pintype "passive"))
      (node (ref "C49") (pin "1") (pinfunction "1_1") (pintype "passive"))
      (node (ref "FB8") (pin "2") (pinfunction "2_2") (pintype "passive"))
      (node (ref "U5") (pin "16") (pinfunction "VDD_16") (pintype "power_in"))
      (node (ref "U5") (pin "20") (pinfunction "VCCO1V8_1_20") (pintype "power_in"))
      (node (ref "U5") (pin "29") (pinfunction "VCCO1V8_0_29") (pintype "power_in"))
    )
    (net (code "249") (name "VOUT_A") (class "Default")
      (node (ref "C57") (pin "1") (pinfunction "1_1") (pintype "passive"))
      (node (ref "FB11") (pin "1") (pinfunction "1_1") (pintype "passive"))
      (node (ref "R17") (pin "2") (pinfunction "2_2") (pintype "passive"))
      (node (ref "U6") (pin "8") (pinfunction "VOUT_8") (pintype "output"))
    )
    (net (code "250") (name "VOUT_B") (class "Default")
      (node (ref "C59") (pin "1") (pinfunction "1_1") (pintype "passive"))
      (node (ref "FB12") (pin "1") (pinfunction "1_1") (pintype "passive"))
      (node (ref "R20") (pin "2") (pinfunction "2_2") (pintype "passive"))
      (node (ref "U7") (pin "8") (pinfunction "VOUT_8") (pintype "output"))
    )
    (net (code "251") (name "VSUP") (class "Default")
      (node (ref "C56") (pin "1") (pinfunction "1_1") (pintype "passive"))
      (node (ref "C58") (pin "1") (pinfunction "1_1") (pintype "passive"))
      (node (ref "JP1") (pin "2") (pinfunction "2_2") (pintype "passive"))
      (node (ref "R18") (pin "2") (pinfunction "2_2") (pintype "passive"))
      (node (ref "R21") (pin "2") (pinfunction "2_2") (pintype "passive"))
      (node (ref "U6") (pin "3") (pinfunction "VIN_3") (pintype "power_in"))
      (node (ref "U6") (pin "4") (pinfunction "VIN_4") (pintype "power_in"))
      (node (ref "U7") (pin "3") (pinfunction "VIN_3") (pintype "power_in"))
      (node (ref "U7") (pin "4") (pinfunction "VIN_4") (pintype "power_in"))
    )
    (net (code "252") (name "V_CLK") (class "Default")
      (node (ref "C1") (pin "1") (pinfunction "1_1") (pintype "passive"))
      (node (ref "FB1") (pin "2") (pinfunction "2_2") (pintype "passive"))
      (node (ref "U1") (pin "6") (pinfunction "VCC_6") (pintype "power_in"))
    )
    (net (code "253") (name "unconnected-(JTAG-Pad12)") (class "Default")
      (node (ref "JTAG") (pin "12") (pinfunction "12_12") (pintype "passive"))
    )
    (net (code "254") (name "unconnected-(JTAG-Pad14)") (class "Default")
      (node (ref "JTAG") (pin "14") (pinfunction "14_14") (pintype "passive"))
    )
    (net (code "255") (name "unconnected-(PCIE-NORTH-PWRGD-PadA11)") (class "Default")
      (node (ref "PCIE-NORTH") (pin "A11") (pinfunction "PWRGD_A11") (pintype "passive"))
    )
    (net (code "256") (name "unconnected-(PCIE-SOUTH-PWRGD-PadA11)") (class "Default")
      (node (ref "PCIE-SOUTH") (pin "A11") (pinfunction "PWRGD_A11") (pintype "passive"))
    )
    (net (code "257") (name "unconnected-(PCIE-SOUTH-SCL-PadB2)") (class "Default")
      (node (ref "PCIE-SOUTH") (pin "B2") (pinfunction "SCL_B2") (pintype "passive"))
    )
    (net (code "258") (name "unconnected-(PCIE-SOUTH-SDA-PadB1)") (class "Default")
      (node (ref "PCIE-SOUTH") (pin "B1") (pinfunction "SDA_B1") (pintype "passive"))
    )
    (net (code "259") (name "unconnected-(PCIE-SOUTH-V_I2C-PadB3)") (class "Default")
      (node (ref "PCIE-SOUTH") (pin "B3") (pinfunction "V_I2C_B3") (pintype "passive"))
    )
  )
)
